# BatteryBoardV1.net
KiCad netlist of a schematic drawn in EAGLE
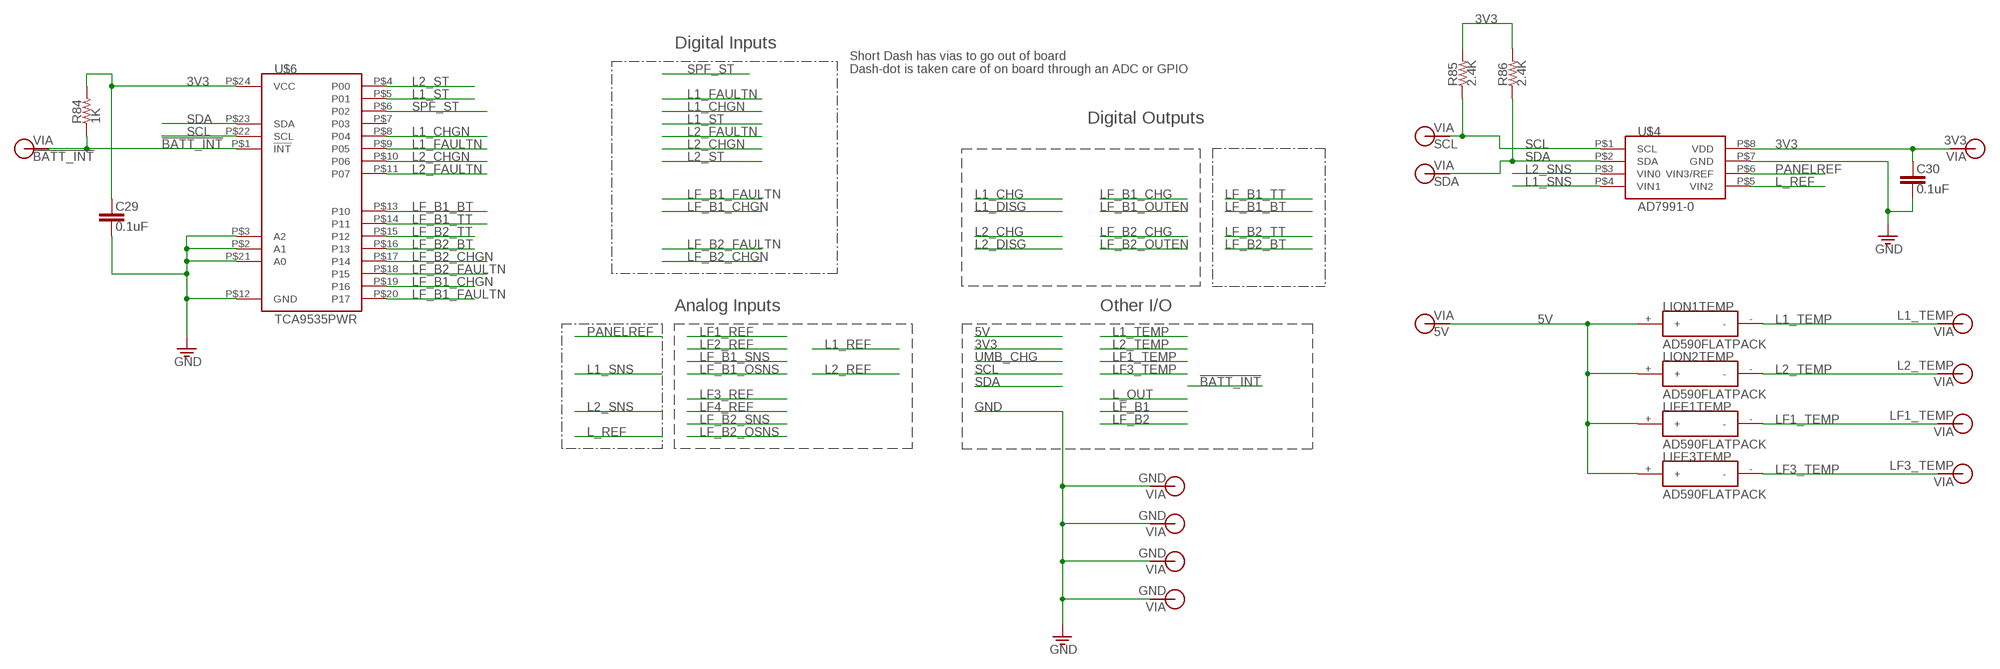
[diagram p0: schematic, sheet 1]
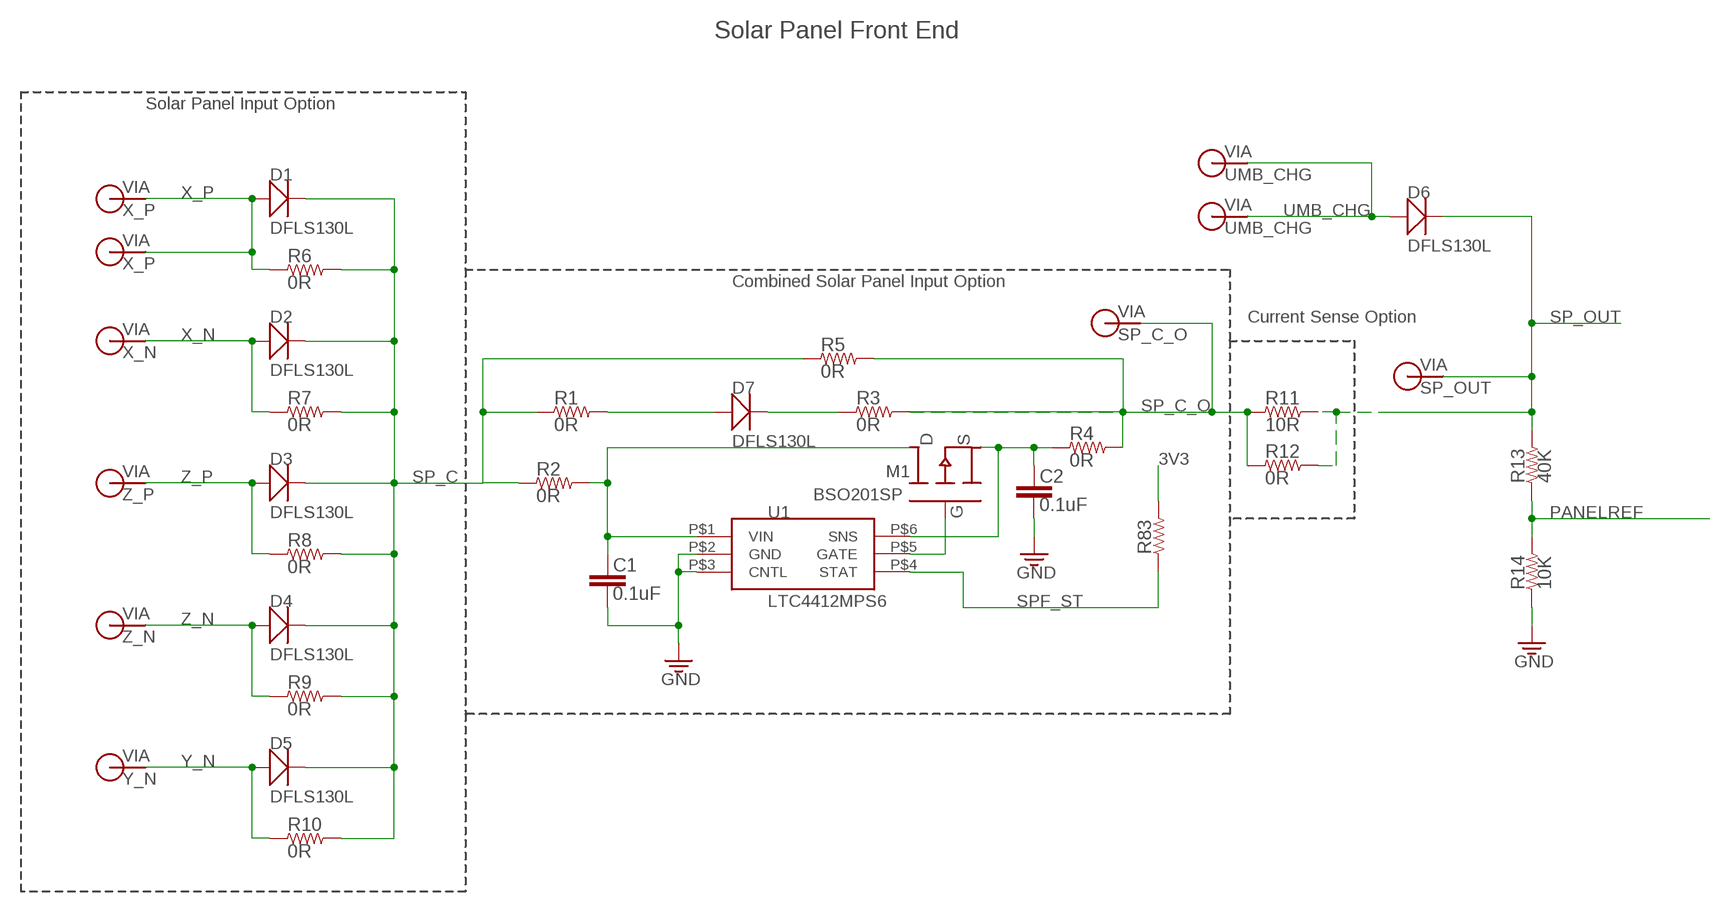
[diagram p1: schematic, sheet 2]
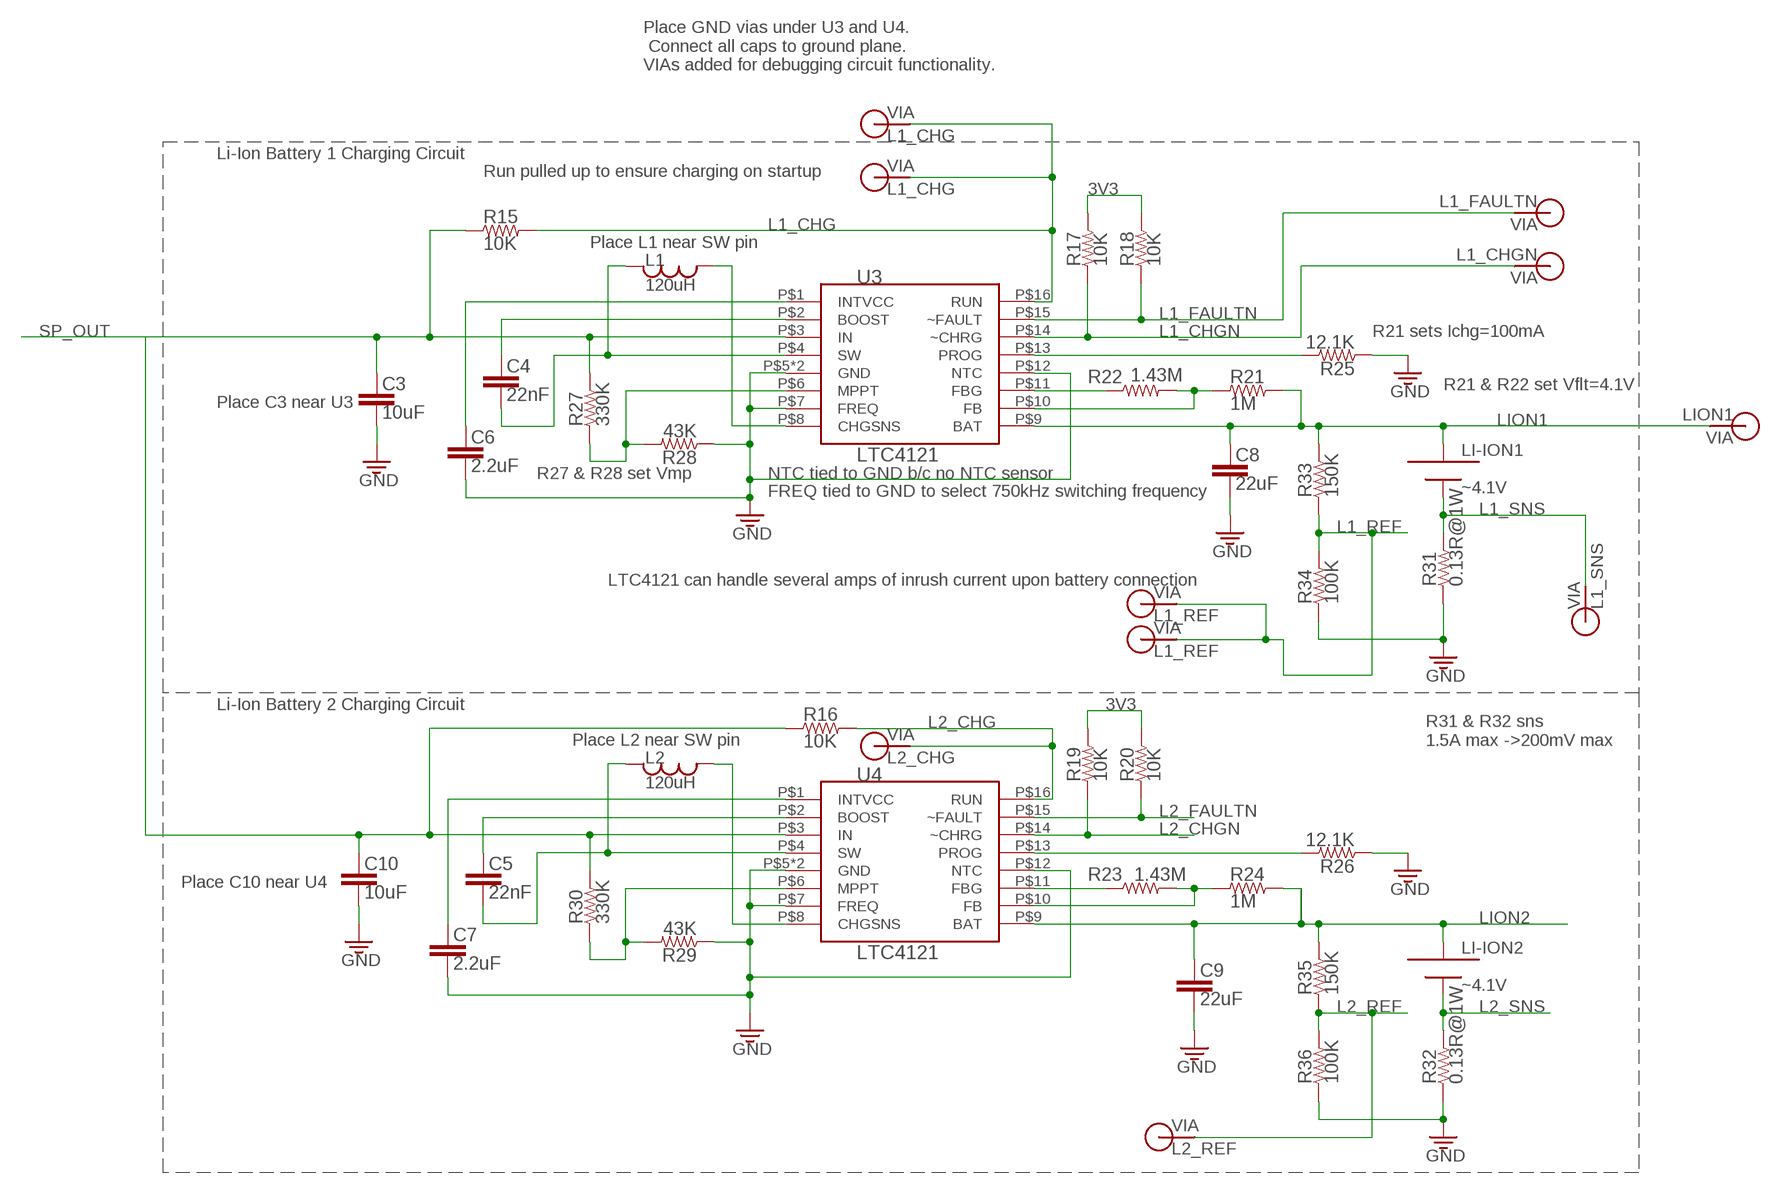
[diagram p2: schematic, sheet 3]
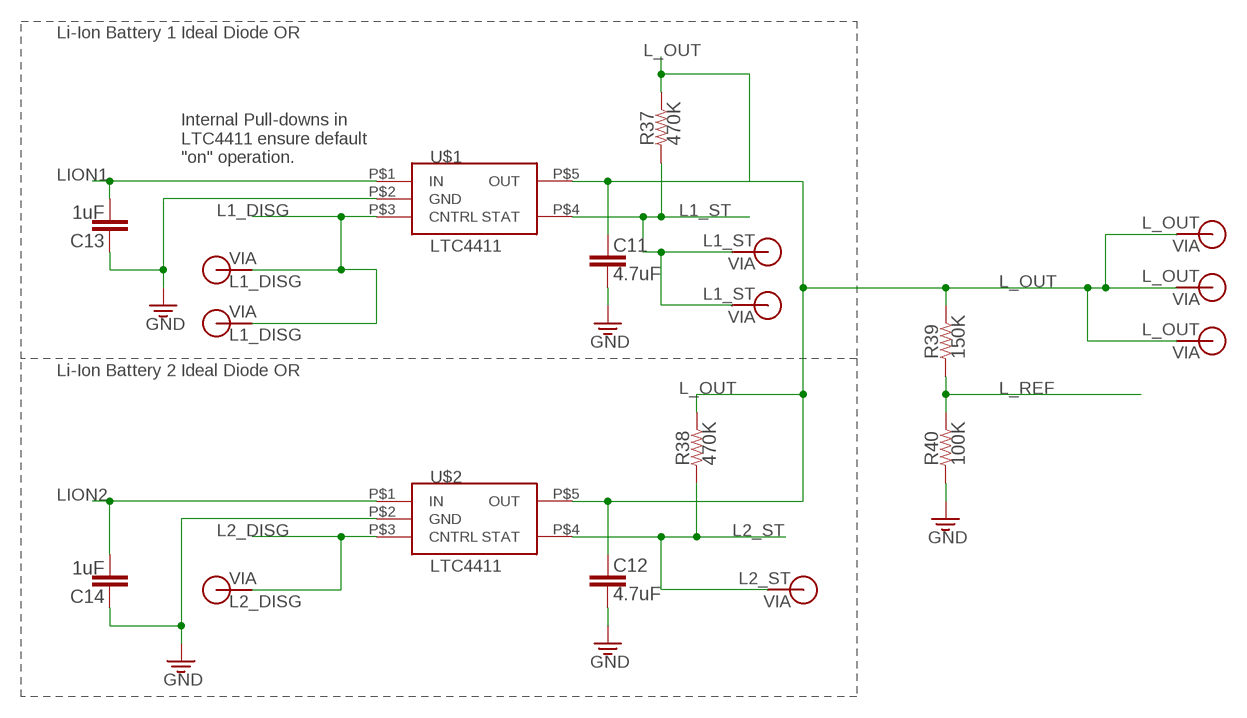
[diagram p3: schematic, sheet 4]
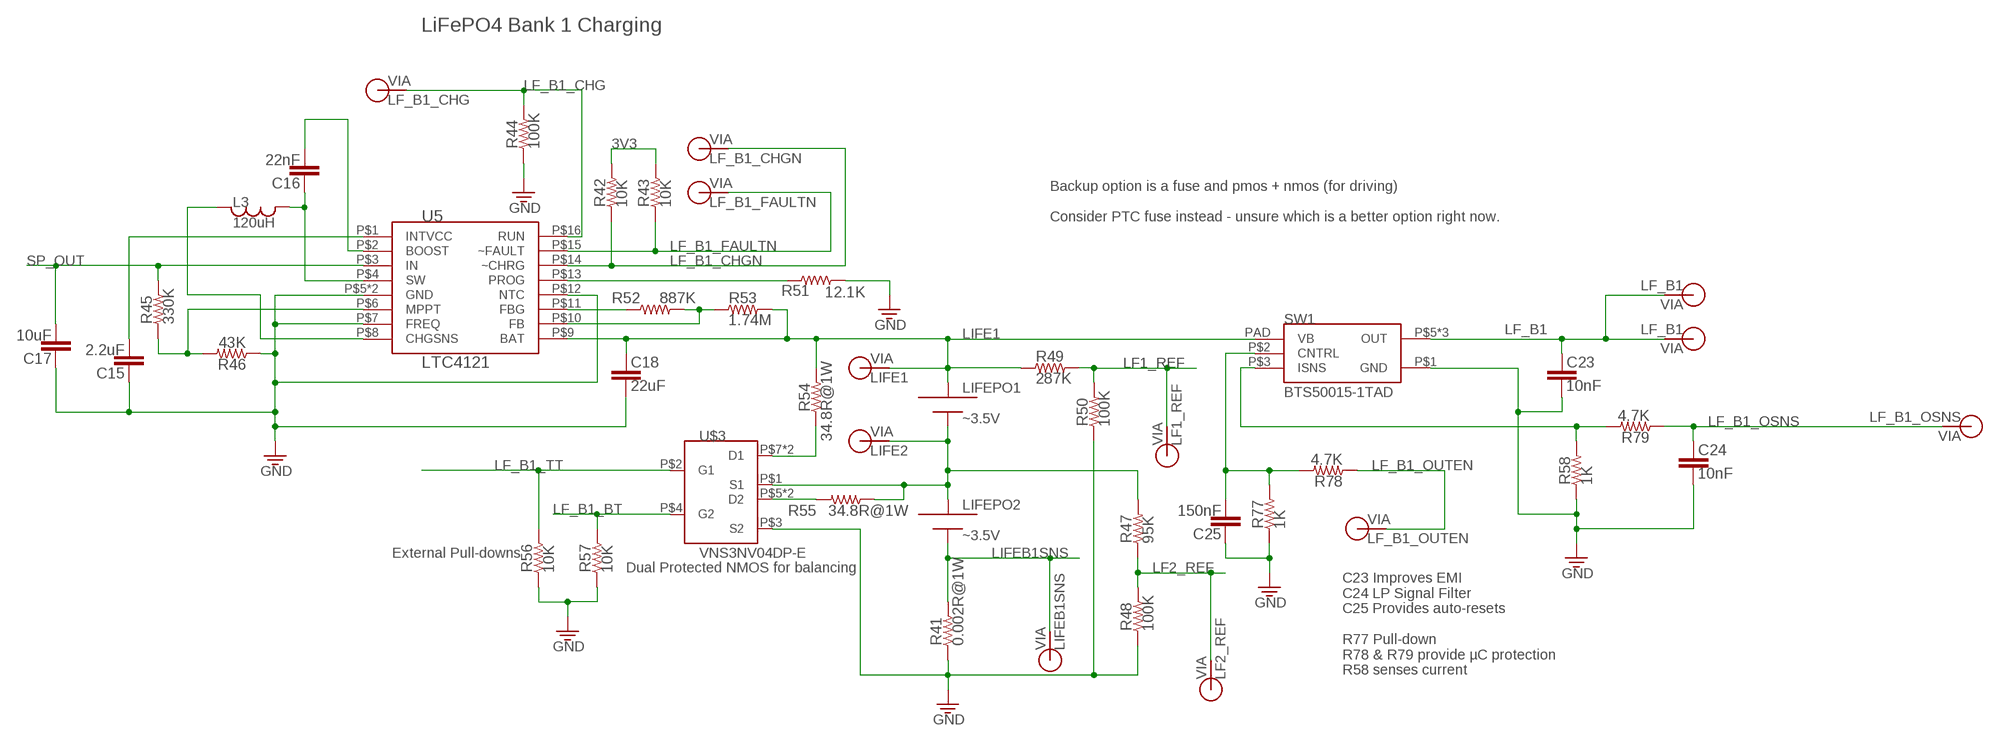
[diagram p4: schematic, sheet 5]
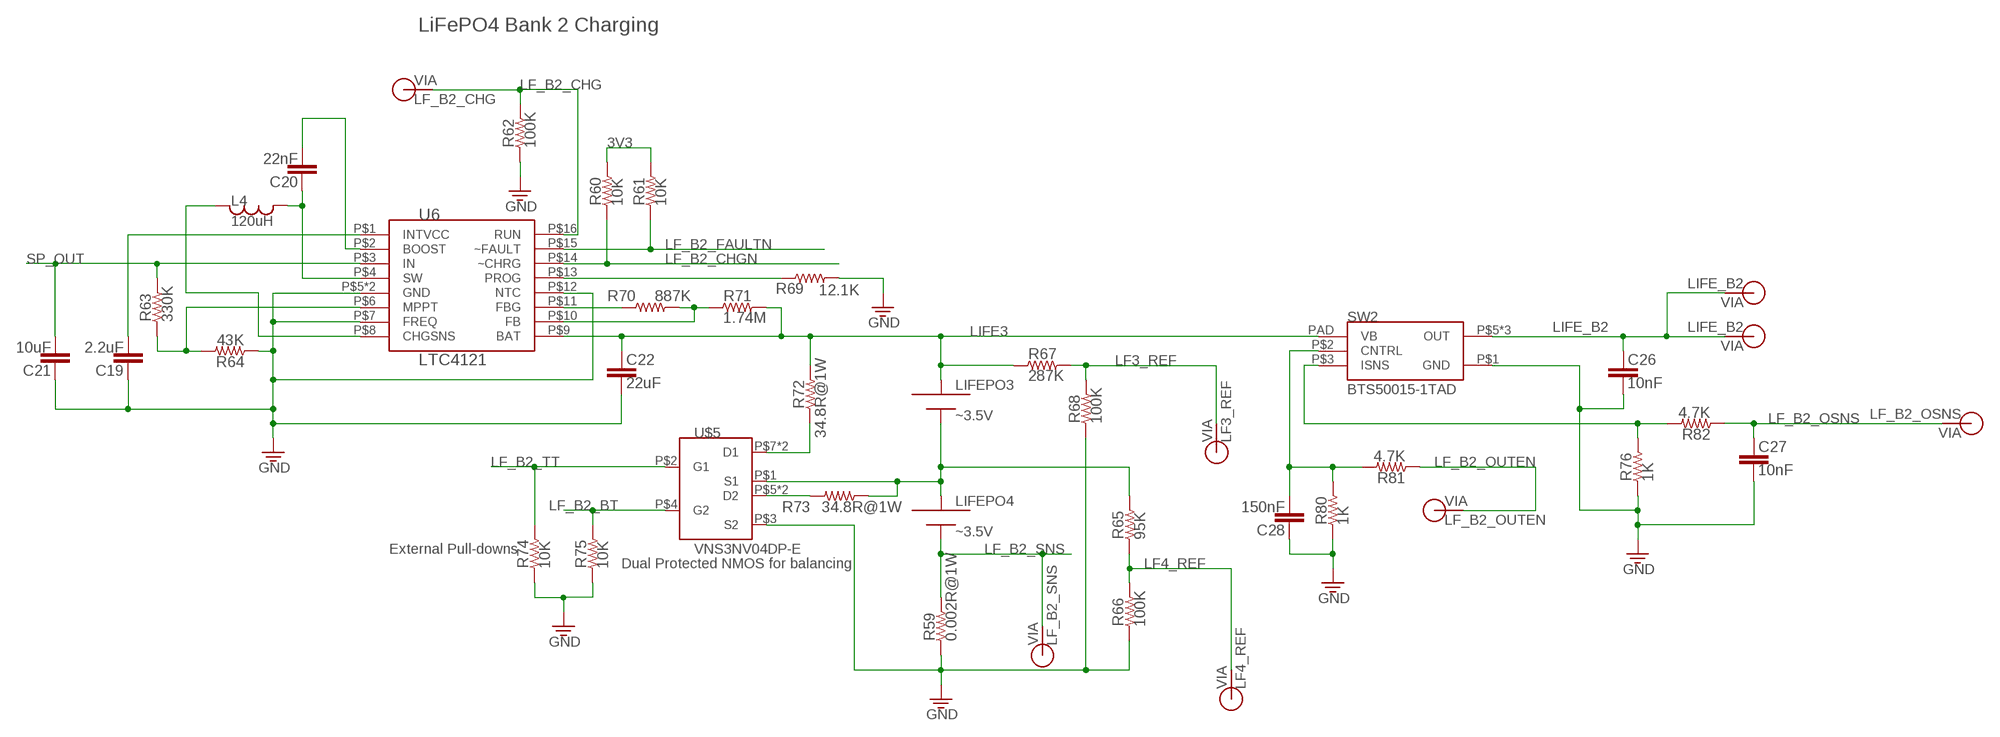
[diagram p5: schematic, sheet 6]

(export (version "E")
  (design (tool "Eeschema 10.0.6"))
  (components
    (comp (ref "C15")
      (value "2.2uF")
      (footprint "eagle-import:0805")
      (libsource (lib "eagle-import") (part "CAP0805"))
    )
    (comp (ref "C16")
      (value "22nF")
      (footprint "eagle-import:0805")
      (libsource (lib "eagle-import") (part "CAP0805"))
    )
    (comp (ref "C17")
      (value "10uF")
      (footprint "eagle-import:0805")
      (libsource (lib "eagle-import") (part "CAP0805"))
    )
    (comp (ref "C18")
      (value "22uF")
      (footprint "eagle-import:0805")
      (libsource (lib "eagle-import") (part "CAP0805"))
    )
    (comp (ref "C23")
      (value "10nF")
      (footprint "eagle-import:0805")
      (libsource (lib "eagle-import") (part "CAP0805"))
    )
    (comp (ref "C24")
      (value "10nF")
      (footprint "eagle-import:0805")
      (libsource (lib "eagle-import") (part "CAP0805"))
    )
    (comp (ref "C25")
      (value "150nF")
      (footprint "eagle-import:0805")
      (libsource (lib "eagle-import") (part "CAP0805"))
    )
    (comp (ref "L3")
      (value "120uH")
      (footprint "eagle-import:1812")
      (libsource (lib "eagle-import") (part "IND1812"))
    )
    (comp (ref "LIFEPO1")
      (value "~3.5V")
      (footprint "eagle-import:EQUISAT-BATTERY-VA")
      (libsource (lib "eagle-import") (part "LIFEPO4VA"))
    )
    (comp (ref "LIFEPO2")
      (value "~3.5V")
      (footprint "eagle-import:EQUISAT-BATTERY-VB")
      (libsource (lib "eagle-import") (part "LIFEPO4VB"))
    )
    (comp (ref "R41")
      (value "0.002R@1W")
      (footprint "eagle-import:1210")
      (libsource (lib "eagle-import") (part "RES1210"))
    )
    (comp (ref "R42")
      (value "10K")
      (footprint "eagle-import:0805")
      (libsource (lib "eagle-import") (part "RES0805"))
    )
    (comp (ref "R43")
      (value "10K")
      (footprint "eagle-import:0805")
      (libsource (lib "eagle-import") (part "RES0805"))
    )
    (comp (ref "R44")
      (value "100K")
      (footprint "eagle-import:0805")
      (libsource (lib "eagle-import") (part "RES0805"))
    )
    (comp (ref "R45")
      (value "330K")
      (footprint "eagle-import:0805")
      (libsource (lib "eagle-import") (part "RES0805"))
    )
    (comp (ref "R46")
      (value "43K")
      (footprint "eagle-import:0805")
      (libsource (lib "eagle-import") (part "RES0805"))
    )
    (comp (ref "R47")
      (value "95K")
      (footprint "eagle-import:0805")
      (libsource (lib "eagle-import") (part "RES0805"))
    )
    (comp (ref "R48")
      (value "100K")
      (footprint "eagle-import:0805")
      (libsource (lib "eagle-import") (part "RES0805"))
    )
    (comp (ref "R49")
      (value "287K")
      (footprint "eagle-import:0805")
      (libsource (lib "eagle-import") (part "RES0805"))
    )
    (comp (ref "R50")
      (value "100K")
      (footprint "eagle-import:0805")
      (libsource (lib "eagle-import") (part "RES0805"))
    )
    (comp (ref "R51")
      (value "12.1K")
      (footprint "eagle-import:0805")
      (libsource (lib "eagle-import") (part "RES0805"))
    )
    (comp (ref "R52")
      (value "887K")
      (footprint "eagle-import:0805")
      (libsource (lib "eagle-import") (part "RES0805"))
    )
    (comp (ref "R53")
      (value "1.74M")
      (footprint "eagle-import:0805")
      (libsource (lib "eagle-import") (part "RES0805"))
    )
    (comp (ref "R54")
      (value "34.8R@1W")
      (footprint "eagle-import:1210")
      (libsource (lib "eagle-import") (part "RES1210"))
    )
    (comp (ref "R55")
      (value "34.8R@1W")
      (footprint "eagle-import:1210")
      (libsource (lib "eagle-import") (part "RES1210"))
    )
    (comp (ref "R56")
      (value "10K")
      (footprint "eagle-import:0805")
      (libsource (lib "eagle-import") (part "RES0805"))
    )
    (comp (ref "R57")
      (value "10K")
      (footprint "eagle-import:0805")
      (libsource (lib "eagle-import") (part "RES0805"))
    )
    (comp (ref "R58")
      (value "1K")
      (footprint "eagle-import:0805")
      (libsource (lib "eagle-import") (part "RES0805"))
    )
    (comp (ref "R77")
      (value "1K")
      (footprint "eagle-import:0805")
      (libsource (lib "eagle-import") (part "RES0805"))
    )
    (comp (ref "R78")
      (value "4.7K")
      (footprint "eagle-import:0805")
      (libsource (lib "eagle-import") (part "RES0805"))
    )
    (comp (ref "R79")
      (value "4.7K")
      (footprint "eagle-import:0805")
      (libsource (lib "eagle-import") (part "RES0805"))
    )
    (comp (ref "SW1")
      (value "BTS50015-1TAD")
      (footprint "eagle-import:TO-263-7-8")
      (libsource (lib "eagle-import") (part "BTS50015-1TAD"))
    )
    (comp (ref "U$3")
      (value "VNS3NV04DP-E")
      (footprint "eagle-import:SO-8")
      (libsource (lib "eagle-import") (part "VNS3NV04DP-E"))
    )
    (comp (ref "U5")
      (value "LTC4121")
      (footprint "eagle-import:QFN-16-PAD")
      (libsource (lib "eagle-import") (part "LTC4121"))
    )
    (comp (ref "V14")
      (value "LIFEB1SNS")
      (footprint "eagle-import:VIA-60MIL")
      (libsource (lib "eagle-import") (part "VIA-60MIL"))
    )
    (comp (ref "V15")
      (value "LF_B1_CHG")
      (footprint "eagle-import:VIA-60MIL")
      (libsource (lib "eagle-import") (part "VIA-60MIL"))
    )
    (comp (ref "V16")
      (value "LIFE2")
      (footprint "eagle-import:VIA-60MIL-SQ")
      (libsource (lib "eagle-import") (part "VIA60MIL-SQ"))
    )
    (comp (ref "V17")
      (value "LIFE1")
      (footprint "eagle-import:VIA-60MIL-SQ")
      (libsource (lib "eagle-import") (part "VIA60MIL-SQ"))
    )
    (comp (ref "V18")
      (value "LF_B1_CHGN")
      (footprint "eagle-import:VIA-60MIL")
      (libsource (lib "eagle-import") (part "VIA-60MIL"))
    )
    (comp (ref "V19")
      (value "LF_B1_FAULTN")
      (footprint "eagle-import:VIA-60MIL")
      (libsource (lib "eagle-import") (part "VIA-60MIL"))
    )
    (comp (ref "V20")
      (value "LF_B1_OUTEN")
      (footprint "eagle-import:VIA-60MIL")
      (libsource (lib "eagle-import") (part "VIA-60MIL"))
    )
    (comp (ref "V21")
      (value "LF_B1")
      (footprint "eagle-import:VIA-120MIL")
      (libsource (lib "eagle-import") (part "VIA-120MIL"))
    )
    (comp (ref "V26")
      (value "LF_B1")
      (footprint "eagle-import:VIA-120MIL")
      (libsource (lib "eagle-import") (part "VIA-120MIL"))
    )
    (comp (ref "V31")
      (value "LF_B1_OSNS")
      (footprint "eagle-import:VIA-60MIL")
      (libsource (lib "eagle-import") (part "VIA-60MIL"))
    )
    (comp (ref "V58")
      (value "LF1_REF")
      (footprint "eagle-import:VIA-60MIL")
      (libsource (lib "eagle-import") (part "VIA-60MIL"))
    )
    (comp (ref "V59")
      (value "LF2_REF")
      (footprint "eagle-import:VIA-60MIL")
      (libsource (lib "eagle-import") (part "VIA-60MIL"))
    )
    (comp (ref "C3")
      (value "10uF")
      (footprint "eagle-import:0805")
      (libsource (lib "eagle-import") (part "CAP0805"))
    )
    (comp (ref "C4")
      (value "22nF")
      (footprint "eagle-import:0805")
      (libsource (lib "eagle-import") (part "CAP0805"))
    )
    (comp (ref "C5")
      (value "22nF")
      (footprint "eagle-import:0805")
      (libsource (lib "eagle-import") (part "CAP0805"))
    )
    (comp (ref "C6")
      (value "2.2uF")
      (footprint "eagle-import:0805")
      (libsource (lib "eagle-import") (part "CAP0805"))
    )
    (comp (ref "C7")
      (value "2.2uF")
      (footprint "eagle-import:0805")
      (libsource (lib "eagle-import") (part "CAP0805"))
    )
    (comp (ref "C8")
      (value "22uF")
      (footprint "eagle-import:0805")
      (libsource (lib "eagle-import") (part "CAP0805"))
    )
    (comp (ref "C9")
      (value "22uF")
      (footprint "eagle-import:0805")
      (libsource (lib "eagle-import") (part "CAP0805"))
    )
    (comp (ref "C10")
      (value "10uF")
      (footprint "eagle-import:0805")
      (libsource (lib "eagle-import") (part "CAP0805"))
    )
    (comp (ref "L1")
      (value "120uH")
      (footprint "eagle-import:1812")
      (libsource (lib "eagle-import") (part "IND1812"))
    )
    (comp (ref "L2")
      (value "120uH")
      (footprint "eagle-import:1812")
      (libsource (lib "eagle-import") (part "IND1812"))
    )
    (comp (ref "LI-ION1")
      (value "~4.1V")
      (footprint "eagle-import:EQUISAT-BATTERY-VA")
      (libsource (lib "eagle-import") (part "LI-ION"))
    )
    (comp (ref "LI-ION2")
      (value "~4.1V")
      (footprint "eagle-import:EQUISAT-BATTERY-VA")
      (libsource (lib "eagle-import") (part "LI-ION"))
    )
    (comp (ref "R15")
      (value "10K")
      (footprint "eagle-import:0805")
      (libsource (lib "eagle-import") (part "RES0805"))
    )
    (comp (ref "R16")
      (value "10K")
      (footprint "eagle-import:0805")
      (libsource (lib "eagle-import") (part "RES0805"))
    )
    (comp (ref "R17")
      (value "10K")
      (footprint "eagle-import:0805")
      (libsource (lib "eagle-import") (part "RES0805"))
    )
    (comp (ref "R18")
      (value "10K")
      (footprint "eagle-import:0805")
      (libsource (lib "eagle-import") (part "RES0805"))
    )
    (comp (ref "R19")
      (value "10K")
      (footprint "eagle-import:0805")
      (libsource (lib "eagle-import") (part "RES0805"))
    )
    (comp (ref "R20")
      (value "10K")
      (footprint "eagle-import:0805")
      (libsource (lib "eagle-import") (part "RES0805"))
    )
    (comp (ref "R21")
      (value "1M")
      (footprint "eagle-import:0805")
      (libsource (lib "eagle-import") (part "RES0805"))
    )
    (comp (ref "R22")
      (value "1.43M")
      (footprint "eagle-import:0805")
      (libsource (lib "eagle-import") (part "RES0805"))
    )
    (comp (ref "R23")
      (value "1.43M")
      (footprint "eagle-import:0805")
      (libsource (lib "eagle-import") (part "RES0805"))
    )
    (comp (ref "R24")
      (value "1M")
      (footprint "eagle-import:0805")
      (libsource (lib "eagle-import") (part "RES0805"))
    )
    (comp (ref "R25")
      (value "12.1K")
      (footprint "eagle-import:0805")
      (libsource (lib "eagle-import") (part "RES0805"))
    )
    (comp (ref "R26")
      (value "12.1K")
      (footprint "eagle-import:0805")
      (libsource (lib "eagle-import") (part "RES0805"))
    )
    (comp (ref "R27")
      (value "330K")
      (footprint "eagle-import:0805")
      (libsource (lib "eagle-import") (part "RES0805"))
    )
    (comp (ref "R28")
      (value "43K")
      (footprint "eagle-import:0805")
      (libsource (lib "eagle-import") (part "RES0805"))
    )
    (comp (ref "R29")
      (value "43K")
      (footprint "eagle-import:0805")
      (libsource (lib "eagle-import") (part "RES0805"))
    )
    (comp (ref "R30")
      (value "330K")
      (footprint "eagle-import:0805")
      (libsource (lib "eagle-import") (part "RES0805"))
    )
    (comp (ref "R31")
      (value "0.13R@1W")
      (footprint "eagle-import:1210")
      (libsource (lib "eagle-import") (part "RES1210"))
    )
    (comp (ref "R32")
      (value "0.13R@1W")
      (footprint "eagle-import:1210")
      (libsource (lib "eagle-import") (part "RES1210"))
    )
    (comp (ref "R33")
      (value "150K")
      (footprint "eagle-import:0805")
      (libsource (lib "eagle-import") (part "RES0805"))
    )
    (comp (ref "R34")
      (value "100K")
      (footprint "eagle-import:0805")
      (libsource (lib "eagle-import") (part "RES0805"))
    )
    (comp (ref "R35")
      (value "150K")
      (footprint "eagle-import:0805")
      (libsource (lib "eagle-import") (part "RES0805"))
    )
    (comp (ref "R36")
      (value "100K")
      (footprint "eagle-import:0805")
      (libsource (lib "eagle-import") (part "RES0805"))
    )
    (comp (ref "U3")
      (value "LTC4121")
      (footprint "eagle-import:QFN-16-PAD")
      (libsource (lib "eagle-import") (part "LTC4121"))
    )
    (comp (ref "U4")
      (value "LTC4121")
      (footprint "eagle-import:QFN-16-PAD")
      (libsource (lib "eagle-import") (part "LTC4121"))
    )
    (comp (ref "V10")
      (value "L1_CHG")
      (footprint "eagle-import:VIA-60MIL")
      (libsource (lib "eagle-import") (part "VIA-60MIL"))
    )
    (comp (ref "V25")
      (value "L1_REF")
      (footprint "eagle-import:VIA-60MIL")
      (libsource (lib "eagle-import") (part "VIA-60MIL"))
    )
    (comp (ref "V29")
      (value "L2_REF")
      (footprint "eagle-import:VIA-60MIL")
      (libsource (lib "eagle-import") (part "VIA-60MIL"))
    )
    (comp (ref "V33")
      (value "L2_CHG")
      (footprint "eagle-import:VIA-60MIL")
      (libsource (lib "eagle-import") (part "VIA-60MIL"))
    )
    (comp (ref "V40")
      (value "L1_CHG")
      (footprint "eagle-import:VIA-60MIL-SQ")
      (libsource (lib "eagle-import") (part "VIA60MIL-SQ"))
    )
    (comp (ref "V41")
      (value "L1_FAULTN")
      (footprint "eagle-import:VIA-60MIL-SQ")
      (libsource (lib "eagle-import") (part "VIA60MIL-SQ"))
    )
    (comp (ref "V42")
      (value "L1_CHGN")
      (footprint "eagle-import:VIA-60MIL-SQ")
      (libsource (lib "eagle-import") (part "VIA60MIL-SQ"))
    )
    (comp (ref "V43")
      (value "L1_SNS")
      (footprint "eagle-import:VIA-60MIL-SQ")
      (libsource (lib "eagle-import") (part "VIA60MIL-SQ"))
    )
    (comp (ref "V44")
      (value "L1_REF")
      (footprint "eagle-import:VIA-60MIL-SQ")
      (libsource (lib "eagle-import") (part "VIA60MIL-SQ"))
    )
    (comp (ref "V45")
      (value "LION1")
      (footprint "eagle-import:VIA-60MIL-SQ")
      (libsource (lib "eagle-import") (part "VIA60MIL-SQ"))
    )
    (comp (ref "C19")
      (value "2.2uF")
      (footprint "eagle-import:0805")
      (libsource (lib "eagle-import") (part "CAP0805"))
    )
    (comp (ref "C20")
      (value "22nF")
      (footprint "eagle-import:0805")
      (libsource (lib "eagle-import") (part "CAP0805"))
    )
    (comp (ref "C21")
      (value "10uF")
      (footprint "eagle-import:0805")
      (libsource (lib "eagle-import") (part "CAP0805"))
    )
    (comp (ref "C22")
      (value "22uF")
      (footprint "eagle-import:0805")
      (libsource (lib "eagle-import") (part "CAP0805"))
    )
    (comp (ref "C26")
      (value "10nF")
      (footprint "eagle-import:0805")
      (libsource (lib "eagle-import") (part "CAP0805"))
    )
    (comp (ref "C27")
      (value "10nF")
      (footprint "eagle-import:0805")
      (libsource (lib "eagle-import") (part "CAP0805"))
    )
    (comp (ref "C28")
      (value "150nF")
      (footprint "eagle-import:0805")
      (libsource (lib "eagle-import") (part "CAP0805"))
    )
    (comp (ref "L4")
      (value "120uH")
      (footprint "eagle-import:1812")
      (libsource (lib "eagle-import") (part "IND1812"))
    )
    (comp (ref "LIFEPO3")
      (value "~3.5V")
      (footprint "eagle-import:EQUISAT-BATTERY-VA")
      (libsource (lib "eagle-import") (part "LIFEPO4VA"))
    )
    (comp (ref "LIFEPO4")
      (value "~3.5V")
      (footprint "eagle-import:EQUISAT-BATTERY-VB")
      (libsource (lib "eagle-import") (part "LIFEPO4VB"))
    )
    (comp (ref "R59")
      (value "0.002R@1W")
      (footprint "eagle-import:1210")
      (libsource (lib "eagle-import") (part "RES1210"))
    )
    (comp (ref "R60")
      (value "10K")
      (footprint "eagle-import:0805")
      (libsource (lib "eagle-import") (part "RES0805"))
    )
    (comp (ref "R61")
      (value "10K")
      (footprint "eagle-import:0805")
      (libsource (lib "eagle-import") (part "RES0805"))
    )
    (comp (ref "R62")
      (value "100K")
      (footprint "eagle-import:0805")
      (libsource (lib "eagle-import") (part "RES0805"))
    )
    (comp (ref "R63")
      (value "330K")
      (footprint "eagle-import:0805")
      (libsource (lib "eagle-import") (part "RES0805"))
    )
    (comp (ref "R64")
      (value "43K")
      (footprint "eagle-import:0805")
      (libsource (lib "eagle-import") (part "RES0805"))
    )
    (comp (ref "R65")
      (value "95K")
      (footprint "eagle-import:0805")
      (libsource (lib "eagle-import") (part "RES0805"))
    )
    (comp (ref "R66")
      (value "100K")
      (footprint "eagle-import:0805")
      (libsource (lib "eagle-import") (part "RES0805"))
    )
    (comp (ref "R67")
      (value "287K")
      (footprint "eagle-import:0805")
      (libsource (lib "eagle-import") (part "RES0805"))
    )
    (comp (ref "R68")
      (value "100K")
      (footprint "eagle-import:0805")
      (libsource (lib "eagle-import") (part "RES0805"))
    )
    (comp (ref "R69")
      (value "12.1K")
      (footprint "eagle-import:0805")
      (libsource (lib "eagle-import") (part "RES0805"))
    )
    (comp (ref "R70")
      (value "887K")
      (footprint "eagle-import:0805")
      (libsource (lib "eagle-import") (part "RES0805"))
    )
    (comp (ref "R71")
      (value "1.74M")
      (footprint "eagle-import:0805")
      (libsource (lib "eagle-import") (part "RES0805"))
    )
    (comp (ref "R72")
      (value "34.8R@1W")
      (footprint "eagle-import:1210")
      (libsource (lib "eagle-import") (part "RES1210"))
    )
    (comp (ref "R73")
      (value "34.8R@1W")
      (footprint "eagle-import:1210")
      (libsource (lib "eagle-import") (part "RES1210"))
    )
    (comp (ref "R74")
      (value "10K")
      (footprint "eagle-import:0805")
      (libsource (lib "eagle-import") (part "RES0805"))
    )
    (comp (ref "R75")
      (value "10K")
      (footprint "eagle-import:0805")
      (libsource (lib "eagle-import") (part "RES0805"))
    )
    (comp (ref "R76")
      (value "1K")
      (footprint "eagle-import:0805")
      (libsource (lib "eagle-import") (part "RES0805"))
    )
    (comp (ref "R80")
      (value "1K")
      (footprint "eagle-import:0805")
      (libsource (lib "eagle-import") (part "RES0805"))
    )
    (comp (ref "R81")
      (value "4.7K")
      (footprint "eagle-import:0805")
      (libsource (lib "eagle-import") (part "RES0805"))
    )
    (comp (ref "R82")
      (value "4.7K")
      (footprint "eagle-import:0805")
      (libsource (lib "eagle-import") (part "RES0805"))
    )
    (comp (ref "SW2")
      (value "BTS50015-1TAD")
      (footprint "eagle-import:TO-263-7-8")
      (libsource (lib "eagle-import") (part "BTS50015-1TAD"))
    )
    (comp (ref "U$5")
      (value "VNS3NV04DP-E")
      (footprint "eagle-import:SO-8")
      (libsource (lib "eagle-import") (part "VNS3NV04DP-E"))
    )
    (comp (ref "U6")
      (value "LTC4121")
      (footprint "eagle-import:QFN-16-PAD")
      (libsource (lib "eagle-import") (part "LTC4121"))
    )
    (comp (ref "V27")
      (value "LIFE_B2")
      (footprint "eagle-import:VIA-120MIL")
      (libsource (lib "eagle-import") (part "VIA-120MIL"))
    )
    (comp (ref "V28")
      (value "LIFE_B2")
      (footprint "eagle-import:VIA-120MIL")
      (libsource (lib "eagle-import") (part "VIA-120MIL"))
    )
    (comp (ref "V56")
      (value "LF_B2_OUTEN")
      (footprint "eagle-import:VIA-60MIL")
      (libsource (lib "eagle-import") (part "VIA-60MIL"))
    )
    (comp (ref "V57")
      (value "LF_B2_CHG")
      (footprint "eagle-import:VIA-60MIL")
      (libsource (lib "eagle-import") (part "VIA-60MIL"))
    )
    (comp (ref "V60")
      (value "LF_B2_SNS")
      (footprint "eagle-import:VIA-60MIL")
      (libsource (lib "eagle-import") (part "VIA-60MIL"))
    )
    (comp (ref "V61")
      (value "LF4_REF")
      (footprint "eagle-import:VIA-60MIL")
      (libsource (lib "eagle-import") (part "VIA-60MIL"))
    )
    (comp (ref "V62")
      (value "LF3_REF")
      (footprint "eagle-import:VIA-60MIL")
      (libsource (lib "eagle-import") (part "VIA-60MIL"))
    )
    (comp (ref "V63")
      (value "LF_B2_OSNS")
      (footprint "eagle-import:VIA-60MIL")
      (libsource (lib "eagle-import") (part "VIA-60MIL"))
    )
    (comp (ref "C11")
      (value "4.7uF")
      (footprint "eagle-import:0805")
      (libsource (lib "eagle-import") (part "CAP0805"))
    )
    (comp (ref "C12")
      (value "4.7uF")
      (footprint "eagle-import:0805")
      (libsource (lib "eagle-import") (part "CAP0805"))
    )
    (comp (ref "C13")
      (value "1uF")
      (footprint "eagle-import:0805")
      (libsource (lib "eagle-import") (part "CAP0805"))
    )
    (comp (ref "C14")
      (value "1uF")
      (footprint "eagle-import:0805")
      (libsource (lib "eagle-import") (part "CAP0805"))
    )
    (comp (ref "R37")
      (value "470K")
      (footprint "eagle-import:0805")
      (libsource (lib "eagle-import") (part "RES0805"))
    )
    (comp (ref "R38")
      (value "470K")
      (footprint "eagle-import:0805")
      (libsource (lib "eagle-import") (part "RES0805"))
    )
    (comp (ref "R39")
      (value "150K")
      (footprint "eagle-import:0805")
      (libsource (lib "eagle-import") (part "RES0805"))
    )
    (comp (ref "R40")
      (value "100K")
      (footprint "eagle-import:0805")
      (libsource (lib "eagle-import") (part "RES0805"))
    )
    (comp (ref "U$1")
      (value "LTC4411")
      (footprint "eagle-import:TSOT23-5")
      (libsource (lib "eagle-import") (part "LTC4411"))
    )
    (comp (ref "U$2")
      (value "LTC4411")
      (footprint "eagle-import:TSOT23-5")
      (libsource (lib "eagle-import") (part "LTC4411"))
    )
    (comp (ref "V30")
      (value "L_OUT")
      (footprint "eagle-import:VIA-120MIL")
      (libsource (lib "eagle-import") (part "VIA-120MIL"))
    )
    (comp (ref "V34")
      (value "L1_DISG")
      (footprint "eagle-import:VIA-60MIL")
      (libsource (lib "eagle-import") (part "VIA-60MIL"))
    )
    (comp (ref "V35")
      (value "L2_DISG")
      (footprint "eagle-import:VIA-60MIL")
      (libsource (lib "eagle-import") (part "VIA-60MIL"))
    )
    (comp (ref "V36")
      (value "L1_ST")
      (footprint "eagle-import:VIA-60MIL")
      (libsource (lib "eagle-import") (part "VIA-60MIL"))
    )
    (comp (ref "V38")
      (value "L2_ST")
      (footprint "eagle-import:VIA-60MIL")
      (libsource (lib "eagle-import") (part "VIA-60MIL"))
    )
    (comp (ref "V46")
      (value "L1_DISG")
      (footprint "eagle-import:VIA-60MIL-SQ")
      (libsource (lib "eagle-import") (part "VIA60MIL-SQ"))
    )
    (comp (ref "V47")
      (value "L1_ST")
      (footprint "eagle-import:VIA-60MIL-SQ")
      (libsource (lib "eagle-import") (part "VIA60MIL-SQ"))
    )
    (comp (ref "V48")
      (value "L_OUT")
      (footprint "eagle-import:VIA-60MIL-SQ")
      (libsource (lib "eagle-import") (part "VIA60MIL-SQ"))
    )
    (comp (ref "V54")
      (value "L_OUT")
      (footprint "eagle-import:VIA-120MIL")
      (libsource (lib "eagle-import") (part "VIA-120MIL"))
    )
    (comp (ref "C29")
      (value "0.1uF")
      (footprint "eagle-import:0805")
      (libsource (lib "eagle-import") (part "CAP0805"))
    )
    (comp (ref "C30")
      (value "0.1uF")
      (footprint "eagle-import:0805")
      (libsource (lib "eagle-import") (part "CAP0805"))
    )
    (comp (ref "LIFE1TEMP")
      (value "AD590FLATPACK")
      (footprint "eagle-import:FLATPACK")
      (libsource (lib "eagle-import") (part "AD590FLATPACK"))
    )
    (comp (ref "LIFE3TEMP")
      (value "AD590FLATPACK")
      (footprint "eagle-import:FLATPACK")
      (libsource (lib "eagle-import") (part "AD590FLATPACK"))
    )
    (comp (ref "LION1TEMP")
      (value "AD590FLATPACK")
      (footprint "eagle-import:FLATPACK")
      (libsource (lib "eagle-import") (part "AD590FLATPACK"))
    )
    (comp (ref "LION2TEMP")
      (value "AD590FLATPACK")
      (footprint "eagle-import:FLATPACK")
      (libsource (lib "eagle-import") (part "AD590FLATPACK"))
    )
    (comp (ref "R84")
      (value "1K")
      (footprint "eagle-import:0805")
      (libsource (lib "eagle-import") (part "RES0805"))
    )
    (comp (ref "R85")
      (value "2.4K")
      (footprint "eagle-import:0805")
      (libsource (lib "eagle-import") (part "RES0805"))
    )
    (comp (ref "R86")
      (value "2.4K")
      (footprint "eagle-import:0805")
      (libsource (lib "eagle-import") (part "RES0805"))
    )
    (comp (ref "U$4")
      (value "AD7991-0")
      (footprint "eagle-import:SOT-23-8")
      (libsource (lib "eagle-import") (part "AD7991-0"))
    )
    (comp (ref "U$6")
      (value "TCA9535PWR")
      (footprint "eagle-import:TSSOP-24")
      (libsource (lib "eagle-import") (part "TCA9535PWR"))
    )
    (comp (ref "V9")
      (value "5V")
      (footprint "eagle-import:VIA-60MIL")
      (libsource (lib "eagle-import") (part "VIA-60MIL"))
    )
    (comp (ref "V11")
      (value "!BATT_INT!")
      (footprint "eagle-import:VIA-60MIL")
      (libsource (lib "eagle-import") (part "VIA-60MIL"))
    )
    (comp (ref "V12")
      (value "GND")
      (footprint "eagle-import:VIA-60MIL-SQ")
      (libsource (lib "eagle-import") (part "VIA60MIL-SQ"))
    )
    (comp (ref "V13")
      (value "GND")
      (footprint "eagle-import:VIA-120MIL")
      (libsource (lib "eagle-import") (part "VIA-120MIL"))
    )
    (comp (ref "V22")
      (value "GND")
      (footprint "eagle-import:VIA-120MIL")
      (libsource (lib "eagle-import") (part "VIA-120MIL"))
    )
    (comp (ref "V23")
      (value "GND")
      (footprint "eagle-import:VIA-120MIL")
      (libsource (lib "eagle-import") (part "VIA-120MIL"))
    )
    (comp (ref "V24")
      (value "L1_TEMP")
      (footprint "eagle-import:VIA-60MIL")
      (libsource (lib "eagle-import") (part "VIA-60MIL"))
    )
    (comp (ref "V32")
      (value "L2_TEMP")
      (footprint "eagle-import:VIA-60MIL")
      (libsource (lib "eagle-import") (part "VIA-60MIL"))
    )
    (comp (ref "V37")
      (value "LF1_TEMP")
      (footprint "eagle-import:VIA-60MIL")
      (libsource (lib "eagle-import") (part "VIA-60MIL"))
    )
    (comp (ref "V50")
      (value "LF3_TEMP")
      (footprint "eagle-import:VIA-60MIL")
      (libsource (lib "eagle-import") (part "VIA-60MIL"))
    )
    (comp (ref "V51")
      (value "3V3")
      (footprint "eagle-import:VIA-60MIL")
      (libsource (lib "eagle-import") (part "VIA-60MIL"))
    )
    (comp (ref "V52")
      (value "SCL")
      (footprint "eagle-import:VIA-60MIL")
      (libsource (lib "eagle-import") (part "VIA-60MIL"))
    )
    (comp (ref "V53")
      (value "SDA")
      (footprint "eagle-import:VIA-60MIL")
      (libsource (lib "eagle-import") (part "VIA-60MIL"))
    )
    (comp (ref "C1")
      (value "0.1uF")
      (footprint "eagle-import:0805")
      (libsource (lib "eagle-import") (part "CAP0805"))
    )
    (comp (ref "C2")
      (value "0.1uF")
      (footprint "eagle-import:0805")
      (libsource (lib "eagle-import") (part "CAP0805"))
    )
    (comp (ref "D1")
      (value "DFLS130L")
      (footprint "eagle-import:PWRDI-123")
      (libsource (lib "eagle-import") (part "DFLS130L"))
    )
    (comp (ref "D2")
      (value "DFLS130L")
      (footprint "eagle-import:PWRDI-123")
      (libsource (lib "eagle-import") (part "DFLS130L"))
    )
    (comp (ref "D3")
      (value "DFLS130L")
      (footprint "eagle-import:PWRDI-123")
      (libsource (lib "eagle-import") (part "DFLS130L"))
    )
    (comp (ref "D4")
      (value "DFLS130L")
      (footprint "eagle-import:PWRDI-123")
      (libsource (lib "eagle-import") (part "DFLS130L"))
    )
    (comp (ref "D5")
      (value "DFLS130L")
      (footprint "eagle-import:PWRDI-123")
      (libsource (lib "eagle-import") (part "DFLS130L"))
    )
    (comp (ref "D6")
      (value "DFLS130L")
      (footprint "eagle-import:PWRDI-123")
      (libsource (lib "eagle-import") (part "DFLS130L"))
    )
    (comp (ref "D7")
      (value "DFLS130L")
      (footprint "eagle-import:PWRDI-123")
      (libsource (lib "eagle-import") (part "DFLS130L"))
    )
    (comp (ref "M1")
      (value "BSO201SP")
      (footprint "eagle-import:SO-8")
      (libsource (lib "eagle-import") (part "BSO201SP"))
    )
    (comp (ref "R1")
      (value "0R")
      (footprint "eagle-import:0805")
      (libsource (lib "eagle-import") (part "RES0805"))
    )
    (comp (ref "R2")
      (value "0R")
      (footprint "eagle-import:0805")
      (libsource (lib "eagle-import") (part "RES0805"))
    )
    (comp (ref "R3")
      (value "0R")
      (footprint "eagle-import:0805")
      (libsource (lib "eagle-import") (part "RES0805"))
    )
    (comp (ref "R4")
      (value "0R")
      (footprint "eagle-import:0805")
      (libsource (lib "eagle-import") (part "RES0805"))
    )
    (comp (ref "R5")
      (value "0R")
      (footprint "eagle-import:0805")
      (libsource (lib "eagle-import") (part "RES0805"))
    )
    (comp (ref "R6")
      (value "0R")
      (footprint "eagle-import:0805")
      (libsource (lib "eagle-import") (part "RES0805"))
    )
    (comp (ref "R7")
      (value "0R")
      (footprint "eagle-import:0805")
      (libsource (lib "eagle-import") (part "RES0805"))
    )
    (comp (ref "R8")
      (value "0R")
      (footprint "eagle-import:0805")
      (libsource (lib "eagle-import") (part "RES0805"))
    )
    (comp (ref "R9")
      (value "0R")
      (footprint "eagle-import:0805")
      (libsource (lib "eagle-import") (part "RES0805"))
    )
    (comp (ref "R10")
      (value "0R")
      (footprint "eagle-import:0805")
      (libsource (lib "eagle-import") (part "RES0805"))
    )
    (comp (ref "R11")
      (value "10R")
      (footprint "eagle-import:0805")
      (libsource (lib "eagle-import") (part "RES0805"))
    )
    (comp (ref "R12")
      (value "0R")
      (footprint "eagle-import:0805")
      (libsource (lib "eagle-import") (part "RES0805"))
    )
    (comp (ref "R13")
      (value "40K")
      (footprint "eagle-import:0805")
      (libsource (lib "eagle-import") (part "RES0805"))
    )
    (comp (ref "R14")
      (value "10K")
      (footprint "eagle-import:0805")
      (libsource (lib "eagle-import") (part "RES0805"))
    )
    (comp (ref "R83")
      (value "RES0805")
      (footprint "eagle-import:0805")
      (libsource (lib "eagle-import") (part "RES0805"))
    )
    (comp (ref "U1")
      (value "LTC4412MPS6")
      (footprint "eagle-import:TSOT23-6")
      (libsource (lib "eagle-import") (part "LTC4412"))
    )
    (comp (ref "V1")
      (value "UMB_CHG")
      (footprint "eagle-import:VIA-60MIL")
      (libsource (lib "eagle-import") (part "VIA-60MIL"))
    )
    (comp (ref "V2")
      (value "X_P")
      (footprint "eagle-import:VIA-60MIL")
      (libsource (lib "eagle-import") (part "VIA-60MIL"))
    )
    (comp (ref "V3")
      (value "X_N")
      (footprint "eagle-import:VIA-60MIL")
      (libsource (lib "eagle-import") (part "VIA-60MIL"))
    )
    (comp (ref "V4")
      (value "Z_P")
      (footprint "eagle-import:VIA-60MIL")
      (libsource (lib "eagle-import") (part "VIA-60MIL"))
    )
    (comp (ref "V5")
      (value "Z_N")
      (footprint "eagle-import:VIA-60MIL")
      (libsource (lib "eagle-import") (part "VIA-60MIL"))
    )
    (comp (ref "V6")
      (value "Y_N")
      (footprint "eagle-import:VIA-60MIL")
      (libsource (lib "eagle-import") (part "VIA-60MIL"))
    )
    (comp (ref "V7")
      (value "SP_C_O")
      (footprint "eagle-import:VIA-60MIL-SQ")
      (libsource (lib "eagle-import") (part "VIA60MIL-SQ"))
    )
    (comp (ref "V8")
      (value "SP_OUT")
      (footprint "eagle-import:VIA-60MIL-SQ")
      (libsource (lib "eagle-import") (part "VIA60MIL-SQ"))
    )
    (comp (ref "V39")
      (value "UMB_CHG")
      (footprint "eagle-import:VIA-60MIL-SQ")
      (libsource (lib "eagle-import") (part "VIA60MIL-SQ"))
    )
    (comp (ref "V49")
      (value "X_P")
      (footprint "eagle-import:VIA-60MIL-SQ")
      (libsource (lib "eagle-import") (part "VIA60MIL-SQ"))
    )
  )
  (nets
    (net (code "1") (name "3V3") (class "Default")
      (node (ref "C29") (pin "1") (pinfunction "P$1_1") (pintype "passive"))
      (node (ref "C30") (pin "1") (pinfunction "P$1_1") (pintype "passive"))
      (node (ref "R17") (pin "2") (pinfunction "2_2") (pintype "passive"))
      (node (ref "R18") (pin "2") (pinfunction "2_2") (pintype "passive"))
      (node (ref "R19") (pin "2") (pinfunction "2_2") (pintype "passive"))
      (node (ref "R20") (pin "2") (pinfunction "2_2") (pintype "passive"))
      (node (ref "R42") (pin "2") (pinfunction "2_2") (pintype "passive"))
      (node (ref "R43") (pin "2") (pinfunction "2_2") (pintype "passive"))
      (node (ref "R60") (pin "2") (pinfunction "2_2") (pintype "passive"))
      (node (ref "R61") (pin "2") (pinfunction "2_2") (pintype "passive"))
      (node (ref "R83") (pin "2") (pinfunction "2_2") (pintype "passive"))
      (node (ref "R84") (pin "2") (pinfunction "2_2") (pintype "passive"))
      (node (ref "R85") (pin "2") (pinfunction "2_2") (pintype "passive"))
      (node (ref "R86") (pin "2") (pinfunction "2_2") (pintype "passive"))
      (node (ref "U$4") (pin "P$8") (pinfunction "VDD_P$8") (pintype "bidirectional"))
      (node (ref "U$6") (pin "P$24") (pinfunction "VCC_P$24") (pintype "power_in"))
      (node (ref "V51") (pin "P$1") (pinfunction "P$1_P$1") (pintype "bidirectional"))
    )
    (net (code "2") (name "5V") (class "Default")
      (node (ref "LIFE1TEMP") (pin "+") (pinfunction "+_+") (pintype "bidirectional"))
      (node (ref "LIFE3TEMP") (pin "+") (pinfunction "+_+") (pintype "bidirectional"))
      (node (ref "LION1TEMP") (pin "+") (pinfunction "+_+") (pintype "bidirectional"))
      (node (ref "LION2TEMP") (pin "+") (pinfunction "+_+") (pintype "bidirectional"))
      (node (ref "V9") (pin "P$1") (pinfunction "P$1_P$1") (pintype "bidirectional"))
    )
    (net (code "3") (name "GND") (class "Default")
      (node (ref "C1") (pin "2") (pinfunction "P$2_2") (pintype "passive"))
      (node (ref "C10") (pin "2") (pinfunction "P$2_2") (pintype "passive"))
      (node (ref "C11") (pin "2") (pinfunction "P$2_2") (pintype "passive"))
      (node (ref "C12") (pin "2") (pinfunction "P$2_2") (pintype "passive"))
      (node (ref "C13") (pin "1") (pinfunction "P$1_1") (pintype "passive"))
      (node (ref "C14") (pin "1") (pinfunction "P$1_1") (pintype "passive"))
      (node (ref "C15") (pin "1") (pinfunction "P$1_1") (pintype "passive"))
      (node (ref "C17") (pin "1") (pinfunction "P$1_1") (pintype "passive"))
      (node (ref "C18") (pin "2") (pinfunction "P$2_2") (pintype "passive"))
      (node (ref "C19") (pin "1") (pinfunction "P$1_1") (pintype "passive"))
      (node (ref "C2") (pin "2") (pinfunction "P$2_2") (pintype "passive"))
      (node (ref "C21") (pin "1") (pinfunction "P$1_1") (pintype "passive"))
      (node (ref "C22") (pin "2") (pinfunction "P$2_2") (pintype "passive"))
      (node (ref "C23") (pin "2") (pinfunction "P$2_2") (pintype "passive"))
      (node (ref "C24") (pin "2") (pinfunction "P$2_2") (pintype "passive"))
      (node (ref "C25") (pin "1") (pinfunction "P$1_1") (pintype "passive"))
      (node (ref "C26") (pin "2") (pinfunction "P$2_2") (pintype "passive"))
      (node (ref "C27") (pin "2") (pinfunction "P$2_2") (pintype "passive"))
      (node (ref "C28") (pin "1") (pinfunction "P$1_1") (pintype "passive"))
      (node (ref "C29") (pin "2") (pinfunction "P$2_2") (pintype "passive"))
      (node (ref "C3") (pin "2") (pinfunction "P$2_2") (pintype "passive"))
      (node (ref "C30") (pin "2") (pinfunction "P$2_2") (pintype "passive"))
      (node (ref "C6") (pin "2") (pinfunction "P$2_2") (pintype "passive"))
      (node (ref "C7") (pin "2") (pinfunction "P$2_2") (pintype "passive"))
      (node (ref "C8") (pin "2") (pinfunction "P$2_2") (pintype "passive"))
      (node (ref "C9") (pin "2") (pinfunction "P$2_2") (pintype "passive"))
      (node (ref "R14") (pin "1") (pinfunction "1_1") (pintype "passive"))
      (node (ref "R25") (pin "1") (pinfunction "1_1") (pintype "passive"))
      (node (ref "R26") (pin "1") (pinfunction "1_1") (pintype "passive"))
      (node (ref "R28") (pin "1") (pinfunction "1_1") (pintype "passive"))
      (node (ref "R29") (pin "1") (pinfunction "1_1") (pintype "passive"))
      (node (ref "R31") (pin "P$1") (pinfunction "1_P$1") (pintype "passive"))
      (node (ref "R32") (pin "P$1") (pinfunction "1_P$1") (pintype "passive"))
      (node (ref "R34") (pin "1") (pinfunction "1_1") (pintype "passive"))
      (node (ref "R36") (pin "1") (pinfunction "1_1") (pintype "passive"))
      (node (ref "R40") (pin "1") (pinfunction "1_1") (pintype "passive"))
      (node (ref "R41") (pin "P$1") (pinfunction "1_P$1") (pintype "passive"))
      (node (ref "R44") (pin "1") (pinfunction "1_1") (pintype "passive"))
      (node (ref "R46") (pin "1") (pinfunction "1_1") (pintype "passive"))
      (node (ref "R48") (pin "1") (pinfunction "1_1") (pintype "passive"))
      (node (ref "R50") (pin "1") (pinfunction "1_1") (pintype "passive"))
      (node (ref "R51") (pin "2") (pinfunction "2_2") (pintype "passive"))
      (node (ref "R56") (pin "1") (pinfunction "1_1") (pintype "passive"))
      (node (ref "R57") (pin "1") (pinfunction "1_1") (pintype "passive"))
      (node (ref "R58") (pin "1") (pinfunction "1_1") (pintype "passive"))
      (node (ref "R59") (pin "P$1") (pinfunction "1_P$1") (pintype "passive"))
      (node (ref "R62") (pin "1") (pinfunction "1_1") (pintype "passive"))
      (node (ref "R64") (pin "1") (pinfunction "1_1") (pintype "passive"))
      (node (ref "R66") (pin "1") (pinfunction "1_1") (pintype "passive"))
      (node (ref "R68") (pin "1") (pinfunction "1_1") (pintype "passive"))
      (node (ref "R69") (pin "2") (pinfunction "2_2") (pintype "passive"))
      (node (ref "R74") (pin "1") (pinfunction "1_1") (pintype "passive"))
      (node (ref "R75") (pin "1") (pinfunction "1_1") (pintype "passive"))
      (node (ref "R76") (pin "1") (pinfunction "1_1") (pintype "passive"))
      (node (ref "R77") (pin "1") (pinfunction "1_1") (pintype "passive"))
      (node (ref "R80") (pin "1") (pinfunction "1_1") (pintype "passive"))
      (node (ref "SW1") (pin "P$1") (pinfunction "GND_P$1") (pintype "bidirectional"))
      (node (ref "SW2") (pin "P$1") (pinfunction "GND_P$1") (pintype "bidirectional"))
      (node (ref "U$1") (pin "P$2") (pinfunction "GND_P$2") (pintype "bidirectional"))
      (node (ref "U$2") (pin "P$2") (pinfunction "GND_P$2") (pintype "bidirectional"))
      (node (ref "U$3") (pin "P$3") (pinfunction "S2_P$3") (pintype "bidirectional"))
      (node (ref "U$4") (pin "P$7") (pinfunction "GND_P$7") (pintype "bidirectional"))
      (node (ref "U$5") (pin "P$3") (pinfunction "S2_P$3") (pintype "bidirectional"))
      (node (ref "U$6") (pin "P$12") (pinfunction "GND_P$12") (pintype "power_in"))
      (node (ref "U$6") (pin "P$2") (pinfunction "A1_P$2") (pintype "bidirectional"))
      (node (ref "U$6") (pin "P$21") (pinfunction "A0_P$21") (pintype "bidirectional"))
      (node (ref "U$6") (pin "P$3") (pinfunction "A2_P$3") (pintype "bidirectional"))
      (node (ref "U1") (pin "P$2") (pinfunction "GND_P$2") (pintype "bidirectional"))
      (node (ref "U1") (pin "P$3") (pinfunction "CNTL_P$3") (pintype "bidirectional"))
      (node (ref "U3") (pin "P$12") (pinfunction "NTC_P$12") (pintype "bidirectional"))
      (node (ref "U3") (pin "P$17") (pinfunction "GND_P$17") (pintype "bidirectional"))
      (node (ref "U3") (pin "P$5") (pinfunction "GND_P$5") (pintype "bidirectional"))
      (node (ref "U3") (pin "P$7") (pinfunction "FREQ_P$7") (pintype "bidirectional"))
      (node (ref "U4") (pin "P$12") (pinfunction "NTC_P$12") (pintype "bidirectional"))
      (node (ref "U4") (pin "P$17") (pinfunction "GND_P$17") (pintype "bidirectional"))
      (node (ref "U4") (pin "P$5") (pinfunction "GND_P$5") (pintype "bidirectional"))
      (node (ref "U4") (pin "P$7") (pinfunction "FREQ_P$7") (pintype "bidirectional"))
      (node (ref "U5") (pin "P$12") (pinfunction "NTC_P$12") (pintype "bidirectional"))
      (node (ref "U5") (pin "P$17") (pinfunction "GND_P$17") (pintype "bidirectional"))
      (node (ref "U5") (pin "P$5") (pinfunction "GND_P$5") (pintype "bidirectional"))
      (node (ref "U5") (pin "P$7") (pinfunction "FREQ_P$7") (pintype "bidirectional"))
      (node (ref "U6") (pin "P$12") (pinfunction "NTC_P$12") (pintype "bidirectional"))
      (node (ref "U6") (pin "P$17") (pinfunction "GND_P$17") (pintype "bidirectional"))
      (node (ref "U6") (pin "P$5") (pinfunction "GND_P$5") (pintype "bidirectional"))
      (node (ref "U6") (pin "P$7") (pinfunction "FREQ_P$7") (pintype "bidirectional"))
      (node (ref "V12") (pin "P$1") (pinfunction "P$1_P$1") (pintype "bidirectional"))
      (node (ref "V13") (pin "P$1") (pinfunction "P$1_P$1") (pintype "bidirectional"))
      (node (ref "V22") (pin "P$1") (pinfunction "P$1_P$1") (pintype "bidirectional"))
      (node (ref "V23") (pin "P$1") (pinfunction "P$1_P$1") (pintype "bidirectional"))
    )
    (net (code "4") (name "L1_CHG") (class "Default")
      (node (ref "R15") (pin "2") (pinfunction "2_2") (pintype "passive"))
      (node (ref "U3") (pin "P$16") (pinfunction "RUN_P$16") (pintype "bidirectional"))
      (node (ref "V10") (pin "P$1") (pinfunction "P$1_P$1") (pintype "bidirectional"))
      (node (ref "V40") (pin "P$1") (pinfunction "P$1_P$1") (pintype "bidirectional"))
    )
    (net (code "5") (name "L1_CHGN") (class "Default")
      (node (ref "R17") (pin "1") (pinfunction "1_1") (pintype "passive"))
      (node (ref "U$6") (pin "P$8") (pinfunction "P04_P$8") (pintype "bidirectional"))
      (node (ref "U3") (pin "P$14") (pinfunction "~{CHRG}_P$14") (pintype "bidirectional"))
      (node (ref "V42") (pin "P$1") (pinfunction "P$1_P$1") (pintype "bidirectional"))
    )
    (net (code "6") (name "L1_DISG") (class "Default")
      (node (ref "U$1") (pin "P$3") (pinfunction "CNTRL_P$3") (pintype "bidirectional"))
      (node (ref "V34") (pin "P$1") (pinfunction "P$1_P$1") (pintype "bidirectional"))
      (node (ref "V46") (pin "P$1") (pinfunction "P$1_P$1") (pintype "bidirectional"))
    )
    (net (code "7") (name "L1_FAULTN") (class "Default")
      (node (ref "R18") (pin "1") (pinfunction "1_1") (pintype "passive"))
      (node (ref "U$6") (pin "P$9") (pinfunction "P05_P$9") (pintype "bidirectional"))
      (node (ref "U3") (pin "P$15") (pinfunction "~{FAULT}_P$15") (pintype "bidirectional"))
      (node (ref "V41") (pin "P$1") (pinfunction "P$1_P$1") (pintype "bidirectional"))
    )
    (net (code "8") (name "L1_REF") (class "Default")
      (node (ref "R33") (pin "1") (pinfunction "1_1") (pintype "passive"))
      (node (ref "R34") (pin "2") (pinfunction "2_2") (pintype "passive"))
      (node (ref "V25") (pin "P$1") (pinfunction "P$1_P$1") (pintype "bidirectional"))
      (node (ref "V44") (pin "P$1") (pinfunction "P$1_P$1") (pintype "bidirectional"))
    )
    (net (code "9") (name "L1_SNS") (class "Default")
      (node (ref "LI-ION1") (pin "MINUS") (pinfunction "MINUS_MINUS") (pintype "power_in"))
      (node (ref "R31") (pin "P$2") (pinfunction "2_P$2") (pintype "passive"))
      (node (ref "U$4") (pin "P$4") (pinfunction "VIN1_P$4") (pintype "bidirectional"))
      (node (ref "V43") (pin "P$1") (pinfunction "P$1_P$1") (pintype "bidirectional"))
    )
    (net (code "10") (name "L1_ST") (class "Default")
      (node (ref "R37") (pin "1") (pinfunction "1_1") (pintype "passive"))
      (node (ref "U$1") (pin "P$4") (pinfunction "STAT_P$4") (pintype "bidirectional"))
      (node (ref "U$6") (pin "P$5") (pinfunction "P01_P$5") (pintype "bidirectional"))
      (node (ref "V36") (pin "P$1") (pinfunction "P$1_P$1") (pintype "bidirectional"))
      (node (ref "V47") (pin "P$1") (pinfunction "P$1_P$1") (pintype "bidirectional"))
    )
    (net (code "11") (name "L1_TEMP") (class "Default")
      (node (ref "LION1TEMP") (pin "-") (pinfunction "-_-") (pintype "bidirectional"))
      (node (ref "V24") (pin "P$1") (pinfunction "P$1_P$1") (pintype "bidirectional"))
    )
    (net (code "12") (name "L2_CHG") (class "Default")
      (node (ref "R16") (pin "2") (pinfunction "2_2") (pintype "passive"))
      (node (ref "U4") (pin "P$16") (pinfunction "RUN_P$16") (pintype "bidirectional"))
      (node (ref "V33") (pin "P$1") (pinfunction "P$1_P$1") (pintype "bidirectional"))
    )
    (net (code "13") (name "L2_CHGN") (class "Default")
      (node (ref "R19") (pin "1") (pinfunction "1_1") (pintype "passive"))
      (node (ref "U$6") (pin "P$10") (pinfunction "P06_P$10") (pintype "bidirectional"))
      (node (ref "U4") (pin "P$14") (pinfunction "~{CHRG}_P$14") (pintype "bidirectional"))
    )
    (net (code "14") (name "L2_DISG") (class "Default")
      (node (ref "U$2") (pin "P$3") (pinfunction "CNTRL_P$3") (pintype "bidirectional"))
      (node (ref "V35") (pin "P$1") (pinfunction "P$1_P$1") (pintype "bidirectional"))
    )
    (net (code "15") (name "L2_FAULTN") (class "Default")
      (node (ref "R20") (pin "1") (pinfunction "1_1") (pintype "passive"))
      (node (ref "U$6") (pin "P$11") (pinfunction "P07_P$11") (pintype "bidirectional"))
      (node (ref "U4") (pin "P$15") (pinfunction "~{FAULT}_P$15") (pintype "bidirectional"))
    )
    (net (code "16") (name "L2_REF") (class "Default")
      (node (ref "R35") (pin "1") (pinfunction "1_1") (pintype "passive"))
      (node (ref "R36") (pin "2") (pinfunction "2_2") (pintype "passive"))
      (node (ref "V29") (pin "P$1") (pinfunction "P$1_P$1") (pintype "bidirectional"))
    )
    (net (code "17") (name "L2_SNS") (class "Default")
      (node (ref "LI-ION2") (pin "MINUS") (pinfunction "MINUS_MINUS") (pintype "power_in"))
      (node (ref "R32") (pin "P$2") (pinfunction "2_P$2") (pintype "passive"))
      (node (ref "U$4") (pin "P$3") (pinfunction "VIN0_P$3") (pintype "bidirectional"))
    )
    (net (code "18") (name "L2_ST") (class "Default")
      (node (ref "R38") (pin "1") (pinfunction "1_1") (pintype "passive"))
      (node (ref "U$2") (pin "P$4") (pinfunction "STAT_P$4") (pintype "bidirectional"))
      (node (ref "U$6") (pin "P$4") (pinfunction "P00_P$4") (pintype "bidirectional"))
      (node (ref "V38") (pin "P$1") (pinfunction "P$1_P$1") (pintype "bidirectional"))
    )
    (net (code "19") (name "L2_TEMP") (class "Default")
      (node (ref "LION2TEMP") (pin "-") (pinfunction "-_-") (pintype "bidirectional"))
      (node (ref "V32") (pin "P$1") (pinfunction "P$1_P$1") (pintype "bidirectional"))
    )
    (net (code "20") (name "LF1_REF") (class "Default")
      (node (ref "R49") (pin "2") (pinfunction "2_2") (pintype "passive"))
      (node (ref "R50") (pin "2") (pinfunction "2_2") (pintype "passive"))
      (node (ref "V58") (pin "P$1") (pinfunction "P$1_P$1") (pintype "bidirectional"))
    )
    (net (code "21") (name "LF1_TEMP") (class "Default")
      (node (ref "LIFE1TEMP") (pin "-") (pinfunction "-_-") (pintype "bidirectional"))
      (node (ref "V37") (pin "P$1") (pinfunction "P$1_P$1") (pintype "bidirectional"))
    )
    (net (code "22") (name "LF2_REF") (class "Default")
      (node (ref "R47") (pin "1") (pinfunction "1_1") (pintype "passive"))
      (node (ref "R48") (pin "2") (pinfunction "2_2") (pintype "passive"))
      (node (ref "V59") (pin "P$1") (pinfunction "P$1_P$1") (pintype "bidirectional"))
    )
    (net (code "23") (name "LF3_REF") (class "Default")
      (node (ref "R67") (pin "2") (pinfunction "2_2") (pintype "passive"))
      (node (ref "R68") (pin "2") (pinfunction "2_2") (pintype "passive"))
      (node (ref "V62") (pin "P$1") (pinfunction "P$1_P$1") (pintype "bidirectional"))
    )
    (net (code "24") (name "LF3_TEMP") (class "Default")
      (node (ref "LIFE3TEMP") (pin "-") (pinfunction "-_-") (pintype "bidirectional"))
      (node (ref "V50") (pin "P$1") (pinfunction "P$1_P$1") (pintype "bidirectional"))
    )
    (net (code "25") (name "LF4_REF") (class "Default")
      (node (ref "R65") (pin "1") (pinfunction "1_1") (pintype "passive"))
      (node (ref "R66") (pin "2") (pinfunction "2_2") (pintype "passive"))
      (node (ref "V61") (pin "P$1") (pinfunction "P$1_P$1") (pintype "bidirectional"))
    )
    (net (code "26") (name "LF_B1") (class "Default")
      (node (ref "C23") (pin "1") (pinfunction "P$1_1") (pintype "passive"))
      (node (ref "SW1") (pin "P$5") (pinfunction "OUT_P$5") (pintype "power_in"))
      (node (ref "SW1") (pin "P$6") (pinfunction "OUT_P$6") (pintype "power_in"))
      (node (ref "SW1") (pin "P$7") (pinfunction "OUT_P$7") (pintype "power_in"))
      (node (ref "V21") (pin "P$1") (pinfunction "P$1_P$1") (pintype "bidirectional"))
      (node (ref "V26") (pin "P$1") (pinfunction "P$1_P$1") (pintype "bidirectional"))
    )
    (net (code "27") (name "LF_B1_BT") (class "Default")
      (node (ref "R57") (pin "2") (pinfunction "2_2") (pintype "passive"))
      (node (ref "U$3") (pin "P$4") (pinfunction "G2_P$4") (pintype "bidirectional"))
      (node (ref "U$6") (pin "P$13") (pinfunction "P10_P$13") (pintype "bidirectional"))
    )
    (net (code "28") (name "LF_B1_CHG") (class "Default")
      (node (ref "R44") (pin "2") (pinfunction "2_2") (pintype "passive"))
      (node (ref "U5") (pin "P$16") (pinfunction "RUN_P$16") (pintype "bidirectional"))
      (node (ref "V15") (pin "P$1") (pinfunction "P$1_P$1") (pintype "bidirectional"))
    )
    (net (code "29") (name "LF_B1_CHGN") (class "Default")
      (node (ref "R42") (pin "1") (pinfunction "1_1") (pintype "passive"))
      (node (ref "U$6") (pin "P$19") (pinfunction "P16_P$19") (pintype "bidirectional"))
      (node (ref "U5") (pin "P$14") (pinfunction "~{CHRG}_P$14") (pintype "bidirectional"))
      (node (ref "V18") (pin "P$1") (pinfunction "P$1_P$1") (pintype "bidirectional"))
    )
    (net (code "30") (name "LF_B1_FAULTN") (class "Default")
      (node (ref "R43") (pin "1") (pinfunction "1_1") (pintype "passive"))
      (node (ref "U$6") (pin "P$20") (pinfunction "P17_P$20") (pintype "bidirectional"))
      (node (ref "U5") (pin "P$15") (pinfunction "~{FAULT}_P$15") (pintype "bidirectional"))
      (node (ref "V19") (pin "P$1") (pinfunction "P$1_P$1") (pintype "bidirectional"))
    )
    (net (code "31") (name "LF_B1_OSNS") (class "Default")
      (node (ref "C24") (pin "1") (pinfunction "P$1_1") (pintype "passive"))
      (node (ref "R79") (pin "1") (pinfunction "1_1") (pintype "passive"))
      (node (ref "V31") (pin "P$1") (pinfunction "P$1_P$1") (pintype "bidirectional"))
    )
    (net (code "32") (name "LF_B1_OUTEN") (class "Default")
      (node (ref "R78") (pin "1") (pinfunction "1_1") (pintype "passive"))
      (node (ref "V20") (pin "P$1") (pinfunction "P$1_P$1") (pintype "bidirectional"))
    )
    (net (code "34") (name "LF_B1_TT") (class "Default")
      (node (ref "R56") (pin "2") (pinfunction "2_2") (pintype "passive"))
      (node (ref "U$3") (pin "P$2") (pinfunction "G1_P$2") (pintype "bidirectional"))
      (node (ref "U$6") (pin "P$14") (pinfunction "P11_P$14") (pintype "bidirectional"))
    )
    (net (code "36") (name "LF_B2_BT") (class "Default")
      (node (ref "R75") (pin "2") (pinfunction "2_2") (pintype "passive"))
      (node (ref "U$5") (pin "P$4") (pinfunction "G2_P$4") (pintype "bidirectional"))
      (node (ref "U$6") (pin "P$16") (pinfunction "P13_P$16") (pintype "bidirectional"))
    )
    (net (code "37") (name "LF_B2_CHG") (class "Default")
      (node (ref "R62") (pin "2") (pinfunction "2_2") (pintype "passive"))
      (node (ref "U6") (pin "P$16") (pinfunction "RUN_P$16") (pintype "bidirectional"))
      (node (ref "V57") (pin "P$1") (pinfunction "P$1_P$1") (pintype "bidirectional"))
    )
    (net (code "38") (name "LF_B2_CHGN") (class "Default")
      (node (ref "R60") (pin "1") (pinfunction "1_1") (pintype "passive"))
      (node (ref "U$6") (pin "P$17") (pinfunction "P14_P$17") (pintype "bidirectional"))
      (node (ref "U6") (pin "P$14") (pinfunction "~{CHRG}_P$14") (pintype "bidirectional"))
    )
    (net (code "39") (name "LF_B2_FAULTN") (class "Default")
      (node (ref "R61") (pin "1") (pinfunction "1_1") (pintype "passive"))
      (node (ref "U$6") (pin "P$18") (pinfunction "P15_P$18") (pintype "bidirectional"))
      (node (ref "U6") (pin "P$15") (pinfunction "~{FAULT}_P$15") (pintype "bidirectional"))
    )
    (net (code "40") (name "LF_B2_OSNS") (class "Default")
      (node (ref "C27") (pin "1") (pinfunction "P$1_1") (pintype "passive"))
      (node (ref "R82") (pin "1") (pinfunction "1_1") (pintype "passive"))
      (node (ref "V63") (pin "P$1") (pinfunction "P$1_P$1") (pintype "bidirectional"))
    )
    (net (code "41") (name "LF_B2_OUTEN") (class "Default")
      (node (ref "R81") (pin "1") (pinfunction "1_1") (pintype "passive"))
      (node (ref "V56") (pin "P$1") (pinfunction "P$1_P$1") (pintype "bidirectional"))
    )
    (net (code "42") (name "LF_B2_SNS") (class "Default")
      (node (ref "LIFEPO4") (pin "MINUS") (pinfunction "MINUS_MINUS") (pintype "power_in"))
      (node (ref "R59") (pin "P$2") (pinfunction "2_P$2") (pintype "passive"))
      (node (ref "V60") (pin "P$1") (pinfunction "P$1_P$1") (pintype "bidirectional"))
    )
    (net (code "43") (name "LF_B2_TT") (class "Default")
      (node (ref "R74") (pin "2") (pinfunction "2_2") (pintype "passive"))
      (node (ref "U$5") (pin "P$2") (pinfunction "G1_P$2") (pintype "bidirectional"))
      (node (ref "U$6") (pin "P$15") (pinfunction "P12_P$15") (pintype "bidirectional"))
    )
    (net (code "44") (name "LIFE1") (class "Default")
      (node (ref "C18") (pin "1") (pinfunction "P$1_1") (pintype "passive"))
      (node (ref "LIFEPO1") (pin "PLUS") (pinfunction "PLUS_PLUS") (pintype "power_in"))
      (node (ref "R49") (pin "1") (pinfunction "1_1") (pintype "passive"))
      (node (ref "R53") (pin "2") (pinfunction "2_2") (pintype "passive"))
      (node (ref "R54") (pin "P$2") (pinfunction "2_P$2") (pintype "passive"))
      (node (ref "SW1") (pin "PAD") (pinfunction "VB_PAD") (pintype "power_in"))
      (node (ref "U5") (pin "P$9") (pinfunction "BAT_P$9") (pintype "bidirectional"))
      (node (ref "V17") (pin "P$1") (pinfunction "P$1_P$1") (pintype "bidirectional"))
    )
    (net (code "45") (name "LIFE3") (class "Default")
      (node (ref "C22") (pin "1") (pinfunction "P$1_1") (pintype "passive"))
      (node (ref "LIFEPO3") (pin "PLUS") (pinfunction "PLUS_PLUS") (pintype "power_in"))
      (node (ref "R67") (pin "1") (pinfunction "1_1") (pintype "passive"))
      (node (ref "R71") (pin "2") (pinfunction "2_2") (pintype "passive"))
      (node (ref "R72") (pin "P$2") (pinfunction "2_P$2") (pintype "passive"))
      (node (ref "SW2") (pin "PAD") (pinfunction "VB_PAD") (pintype "power_in"))
      (node (ref "U6") (pin "P$9") (pinfunction "BAT_P$9") (pintype "bidirectional"))
    )
    (net (code "46") (name "LIFEB1SNS") (class "Default")
      (node (ref "LIFEPO2") (pin "MINUS") (pinfunction "MINUS_MINUS") (pintype "power_in"))
      (node (ref "R41") (pin "P$2") (pinfunction "2_P$2") (pintype "passive"))
      (node (ref "V14") (pin "P$1") (pinfunction "P$1_P$1") (pintype "bidirectional"))
    )
    (net (code "47") (name "LIFE_B2") (class "Default")
      (node (ref "C26") (pin "1") (pinfunction "P$1_1") (pintype "passive"))
      (node (ref "SW2") (pin "P$5") (pinfunction "OUT_P$5") (pintype "power_in"))
      (node (ref "SW2") (pin "P$6") (pinfunction "OUT_P$6") (pintype "power_in"))
      (node (ref "SW2") (pin "P$7") (pinfunction "OUT_P$7") (pintype "power_in"))
      (node (ref "V27") (pin "P$1") (pinfunction "P$1_P$1") (pintype "bidirectional"))
      (node (ref "V28") (pin "P$1") (pinfunction "P$1_P$1") (pintype "bidirectional"))
    )
    (net (code "48") (name "LION1") (class "Default")
      (node (ref "C13") (pin "2") (pinfunction "P$2_2") (pintype "passive"))
      (node (ref "C8") (pin "1") (pinfunction "P$1_1") (pintype "passive"))
      (node (ref "LI-ION1") (pin "PLUS") (pinfunction "PLUS_PLUS") (pintype "power_in"))
      (node (ref "R21") (pin "2") (pinfunction "2_2") (pintype "passive"))
      (node (ref "R33") (pin "2") (pinfunction "2_2") (pintype "passive"))
      (node (ref "U$1") (pin "P$1") (pinfunction "IN_P$1") (pintype "bidirectional"))
      (node (ref "U3") (pin "P$9") (pinfunction "BAT_P$9") (pintype "bidirectional"))
      (node (ref "V45") (pin "P$1") (pinfunction "P$1_P$1") (pintype "bidirectional"))
    )
    (net (code "49") (name "LION2") (class "Default")
      (node (ref "C14") (pin "2") (pinfunction "P$2_2") (pintype "passive"))
      (node (ref "C9") (pin "1") (pinfunction "P$1_1") (pintype "passive"))
      (node (ref "LI-ION2") (pin "PLUS") (pinfunction "PLUS_PLUS") (pintype "power_in"))
      (node (ref "R24") (pin "2") (pinfunction "2_2") (pintype "passive"))
      (node (ref "R35") (pin "2") (pinfunction "2_2") (pintype "passive"))
      (node (ref "U$2") (pin "P$1") (pinfunction "IN_P$1") (pintype "bidirectional"))
      (node (ref "U4") (pin "P$9") (pinfunction "BAT_P$9") (pintype "bidirectional"))
    )
    (net (code "50") (name "L_OUT") (class "Default")
      (node (ref "C11") (pin "1") (pinfunction "P$1_1") (pintype "passive"))
      (node (ref "C12") (pin "1") (pinfunction "P$1_1") (pintype "passive"))
      (node (ref "R37") (pin "2") (pinfunction "2_2") (pintype "passive"))
      (node (ref "R38") (pin "2") (pinfunction "2_2") (pintype "passive"))
      (node (ref "R39") (pin "2") (pinfunction "2_2") (pintype "passive"))
      (node (ref "U$1") (pin "P$5") (pinfunction "OUT_P$5") (pintype "bidirectional"))
      (node (ref "U$2") (pin "P$5") (pinfunction "OUT_P$5") (pintype "bidirectional"))
      (node (ref "V30") (pin "P$1") (pinfunction "P$1_P$1") (pintype "bidirectional"))
      (node (ref "V48") (pin "P$1") (pinfunction "P$1_P$1") (pintype "bidirectional"))
      (node (ref "V54") (pin "P$1") (pinfunction "P$1_P$1") (pintype "bidirectional"))
    )
    (net (code "51") (name "L_REF") (class "Default")
      (node (ref "R39") (pin "1") (pinfunction "1_1") (pintype "passive"))
      (node (ref "R40") (pin "2") (pinfunction "2_2") (pintype "passive"))
      (node (ref "U$4") (pin "P$5") (pinfunction "VIN2_P$5") (pintype "bidirectional"))
    )
    (net (code "52") (name "Net-(C1-P$1)") (class "Default")
      (node (ref "C1") (pin "1") (pinfunction "P$1_1") (pintype "passive"))
      (node (ref "M1") (pin "P$5") (pinfunction "D_P$5") (pintype "bidirectional"))
      (node (ref "M1") (pin "P$6") (pinfunction "D_P$6") (pintype "bidirectional"))
      (node (ref "M1") (pin "P$7") (pinfunction "D_P$7") (pintype "bidirectional"))
      (node (ref "M1") (pin "P$8") (pinfunction "D_P$8") (pintype "bidirectional"))
      (node (ref "R2") (pin "2") (pinfunction "2_2") (pintype "passive"))
      (node (ref "U1") (pin "P$1") (pinfunction "VIN_P$1") (pintype "bidirectional"))
    )
    (net (code "53") (name "Net-(C2-P$1)") (class "Default")
      (node (ref "C2") (pin "1") (pinfunction "P$1_1") (pintype "passive"))
      (node (ref "M1") (pin "P$1") (pinfunction "S_P$1") (pintype "bidirectional"))
      (node (ref "M1") (pin "P$2") (pinfunction "S_P$2") (pintype "bidirectional"))
      (node (ref "M1") (pin "P$3") (pinfunction "S_P$3") (pintype "bidirectional"))
      (node (ref "R4") (pin "1") (pinfunction "1_1") (pintype "passive"))
      (node (ref "U1") (pin "P$6") (pinfunction "SNS_P$6") (pintype "bidirectional"))
    )
    (net (code "54") (name "Net-(C4-P$1)") (class "Default")
      (node (ref "C4") (pin "1") (pinfunction "P$1_1") (pintype "passive"))
      (node (ref "U3") (pin "P$2") (pinfunction "BOOST_P$2") (pintype "bidirectional"))
    )
    (net (code "55") (name "Net-(C4-P$2)") (class "Default")
      (node (ref "C4") (pin "2") (pinfunction "P$2_2") (pintype "passive"))
      (node (ref "L1") (pin "P$1") (pinfunction "P$1_P$1") (pintype "passive"))
      (node (ref "U3") (pin "P$4") (pinfunction "SW_P$4") (pintype "bidirectional"))
    )
    (net (code "56") (name "Net-(C5-P$1)") (class "Default")
      (node (ref "C5") (pin "1") (pinfunction "P$1_1") (pintype "passive"))
      (node (ref "U4") (pin "P$2") (pinfunction "BOOST_P$2") (pintype "bidirectional"))
    )
    (net (code "57") (name "Net-(C5-P$2)") (class "Default")
      (node (ref "C5") (pin "2") (pinfunction "P$2_2") (pintype "passive"))
      (node (ref "L2") (pin "P$1") (pinfunction "P$1_P$1") (pintype "passive"))
      (node (ref "U4") (pin "P$4") (pinfunction "SW_P$4") (pintype "bidirectional"))
    )
    (net (code "58") (name "Net-(C6-P$1)") (class "Default")
      (node (ref "C6") (pin "1") (pinfunction "P$1_1") (pintype "passive"))
      (node (ref "U3") (pin "P$1") (pinfunction "INTVCC_P$1") (pintype "bidirectional"))
    )
    (net (code "59") (name "Net-(C7-P$1)") (class "Default")
      (node (ref "C7") (pin "1") (pinfunction "P$1_1") (pintype "passive"))
      (node (ref "U4") (pin "P$1") (pinfunction "INTVCC_P$1") (pintype "bidirectional"))
    )
    (net (code "60") (name "Net-(C15-P$2)") (class "Default")
      (node (ref "C15") (pin "2") (pinfunction "P$2_2") (pintype "passive"))
      (node (ref "U5") (pin "P$1") (pinfunction "INTVCC_P$1") (pintype "bidirectional"))
    )
    (net (code "61") (name "Net-(C16-P$1)") (class "Default")
      (node (ref "C16") (pin "1") (pinfunction "P$1_1") (pintype "passive"))
      (node (ref "L3") (pin "P$2") (pinfunction "P$2_P$2") (pintype "passive"))
      (node (ref "U5") (pin "P$4") (pinfunction "SW_P$4") (pintype "bidirectional"))
    )
    (net (code "62") (name "Net-(C16-P$2)") (class "Default")
      (node (ref "C16") (pin "2") (pinfunction "P$2_2") (pintype "passive"))
      (node (ref "U5") (pin "P$2") (pinfunction "BOOST_P$2") (pintype "bidirectional"))
    )
    (net (code "63") (name "Net-(C19-P$2)") (class "Default")
      (node (ref "C19") (pin "2") (pinfunction "P$2_2") (pintype "passive"))
      (node (ref "U6") (pin "P$1") (pinfunction "INTVCC_P$1") (pintype "bidirectional"))
    )
    (net (code "64") (name "Net-(C20-P$1)") (class "Default")
      (node (ref "C20") (pin "1") (pinfunction "P$1_1") (pintype "passive"))
      (node (ref "L4") (pin "P$2") (pinfunction "P$2_P$2") (pintype "passive"))
      (node (ref "U6") (pin "P$4") (pinfunction "SW_P$4") (pintype "bidirectional"))
    )
    (net (code "65") (name "Net-(C20-P$2)") (class "Default")
      (node (ref "C20") (pin "2") (pinfunction "P$2_2") (pintype "passive"))
      (node (ref "U6") (pin "P$2") (pinfunction "BOOST_P$2") (pintype "bidirectional"))
    )
    (net (code "66") (name "Net-(C25-P$2)") (class "Default")
      (node (ref "C25") (pin "2") (pinfunction "P$2_2") (pintype "passive"))
      (node (ref "R77") (pin "2") (pinfunction "2_2") (pintype "passive"))
      (node (ref "R78") (pin "2") (pinfunction "2_2") (pintype "passive"))
      (node (ref "SW1") (pin "P$2") (pinfunction "CNTRL_P$2") (pintype "input"))
    )
    (net (code "67") (name "Net-(C28-P$2)") (class "Default")
      (node (ref "C28") (pin "2") (pinfunction "P$2_2") (pintype "passive"))
      (node (ref "R80") (pin "2") (pinfunction "2_2") (pintype "passive"))
      (node (ref "R81") (pin "2") (pinfunction "2_2") (pintype "passive"))
      (node (ref "SW2") (pin "P$2") (pinfunction "CNTRL_P$2") (pintype "input"))
    )
    (net (code "68") (name "Net-(D7-PadA)") (class "Default")
      (node (ref "D7") (pin "A") (pinfunction "A_A") (pintype "bidirectional"))
      (node (ref "R1") (pin "2") (pinfunction "2_2") (pintype "passive"))
    )
    (net (code "69") (name "Net-(D7-PadC)") (class "Default")
      (node (ref "D7") (pin "C") (pinfunction "C_C") (pintype "bidirectional"))
      (node (ref "R3") (pin "1") (pinfunction "1_1") (pintype "passive"))
    )
    (net (code "70") (name "Net-(M1-G)") (class "Default")
      (node (ref "M1") (pin "P$4") (pinfunction "G_P$4") (pintype "bidirectional"))
      (node (ref "U1") (pin "P$5") (pinfunction "GATE_P$5") (pintype "bidirectional"))
    )
    (net (code "71") (name "Net-(R54-1)") (class "Default")
      (node (ref "R54") (pin "P$1") (pinfunction "1_P$1") (pintype "passive"))
      (node (ref "U$3") (pin "P$7") (pinfunction "D1_P$7") (pintype "bidirectional"))
      (node (ref "U$3") (pin "P$8") (pinfunction "D1_P$8") (pintype "bidirectional"))
    )
    (net (code "72") (name "Net-(R55-1)") (class "Default")
      (node (ref "LIFEPO1") (pin "MINUS") (pinfunction "MINUS_MINUS") (pintype "power_in"))
      (node (ref "LIFEPO2") (pin "PLUS") (pinfunction "PLUS_PLUS") (pintype "power_in"))
      (node (ref "R47") (pin "2") (pinfunction "2_2") (pintype "passive"))
      (node (ref "R55") (pin "P$1") (pinfunction "1_P$1") (pintype "passive"))
      (node (ref "U$3") (pin "P$1") (pinfunction "S1_P$1") (pintype "bidirectional"))
      (node (ref "V16") (pin "P$1") (pinfunction "P$1_P$1") (pintype "bidirectional"))
    )
    (net (code "73") (name "Net-(R55-2)") (class "Default")
      (node (ref "R55") (pin "P$2") (pinfunction "2_P$2") (pintype "passive"))
      (node (ref "U$3") (pin "P$5") (pinfunction "D2_P$5") (pintype "bidirectional"))
      (node (ref "U$3") (pin "P$6") (pinfunction "D2_P$6") (pintype "bidirectional"))
    )
    (net (code "74") (name "Net-(R72-1)") (class "Default")
      (node (ref "R72") (pin "P$1") (pinfunction "1_P$1") (pintype "passive"))
      (node (ref "U$5") (pin "P$7") (pinfunction "D1_P$7") (pintype "bidirectional"))
      (node (ref "U$5") (pin "P$8") (pinfunction "D1_P$8") (pintype "bidirectional"))
    )
    (net (code "75") (name "Net-(R73-1)") (class "Default")
      (node (ref "LIFEPO3") (pin "MINUS") (pinfunction "MINUS_MINUS") (pintype "power_in"))
      (node (ref "LIFEPO4") (pin "PLUS") (pinfunction "PLUS_PLUS") (pintype "power_in"))
      (node (ref "R65") (pin "2") (pinfunction "2_2") (pintype "passive"))
      (node (ref "R73") (pin "P$1") (pinfunction "1_P$1") (pintype "passive"))
      (node (ref "U$5") (pin "P$1") (pinfunction "S1_P$1") (pintype "bidirectional"))
    )
    (net (code "76") (name "Net-(R73-2)") (class "Default")
      (node (ref "R73") (pin "P$2") (pinfunction "2_P$2") (pintype "passive"))
      (node (ref "U$5") (pin "P$5") (pinfunction "D2_P$5") (pintype "bidirectional"))
      (node (ref "U$5") (pin "P$6") (pinfunction "D2_P$6") (pintype "bidirectional"))
    )
    (net (code "77") (name "Net-(SW1-ISNS)") (class "Default")
      (node (ref "R58") (pin "2") (pinfunction "2_2") (pintype "passive"))
      (node (ref "R79") (pin "2") (pinfunction "2_2") (pintype "passive"))
      (node (ref "SW1") (pin "P$3") (pinfunction "ISNS_P$3") (pintype "output"))
    )
    (net (code "78") (name "Net-(SW2-ISNS)") (class "Default")
      (node (ref "R76") (pin "2") (pinfunction "2_2") (pintype "passive"))
      (node (ref "R82") (pin "2") (pinfunction "2_2") (pintype "passive"))
      (node (ref "SW2") (pin "P$3") (pinfunction "ISNS_P$3") (pintype "output"))
    )
    (net (code "79") (name "Net-(U3-CHGSNS)") (class "Default")
      (node (ref "L1") (pin "P$2") (pinfunction "P$2_P$2") (pintype "passive"))
      (node (ref "U3") (pin "P$8") (pinfunction "CHGSNS_P$8") (pintype "bidirectional"))
    )
    (net (code "80") (name "Net-(U3-FB)") (class "Default")
      (node (ref "R21") (pin "1") (pinfunction "1_1") (pintype "passive"))
      (node (ref "R22") (pin "2") (pinfunction "2_2") (pintype "passive"))
      (node (ref "U3") (pin "P$10") (pinfunction "FB_P$10") (pintype "bidirectional"))
    )
    (net (code "81") (name "Net-(U3-FBG)") (class "Default")
      (node (ref "R22") (pin "1") (pinfunction "1_1") (pintype "passive"))
      (node (ref "U3") (pin "P$11") (pinfunction "FBG_P$11") (pintype "bidirectional"))
    )
    (net (code "82") (name "Net-(U3-MPPT)") (class "Default")
      (node (ref "R27") (pin "1") (pinfunction "1_1") (pintype "passive"))
      (node (ref "R28") (pin "2") (pinfunction "2_2") (pintype "passive"))
      (node (ref "U3") (pin "P$6") (pinfunction "MPPT_P$6") (pintype "bidirectional"))
    )
    (net (code "83") (name "Net-(U3-PROG)") (class "Default")
      (node (ref "R25") (pin "2") (pinfunction "2_2") (pintype "passive"))
      (node (ref "U3") (pin "P$13") (pinfunction "PROG_P$13") (pintype "bidirectional"))
    )
    (net (code "84") (name "Net-(U4-CHGSNS)") (class "Default")
      (node (ref "L2") (pin "P$2") (pinfunction "P$2_P$2") (pintype "passive"))
      (node (ref "U4") (pin "P$8") (pinfunction "CHGSNS_P$8") (pintype "bidirectional"))
    )
    (net (code "85") (name "Net-(U4-FB)") (class "Default")
      (node (ref "R23") (pin "2") (pinfunction "2_2") (pintype "passive"))
      (node (ref "R24") (pin "1") (pinfunction "1_1") (pintype "passive"))
      (node (ref "U4") (pin "P$10") (pinfunction "FB_P$10") (pintype "bidirectional"))
    )
    (net (code "86") (name "Net-(U4-FBG)") (class "Default")
      (node (ref "R23") (pin "1") (pinfunction "1_1") (pintype "passive"))
      (node (ref "U4") (pin "P$11") (pinfunction "FBG_P$11") (pintype "bidirectional"))
    )
    (net (code "87") (name "Net-(U4-MPPT)") (class "Default")
      (node (ref "R29") (pin "2") (pinfunction "2_2") (pintype "passive"))
      (node (ref "R30") (pin "1") (pinfunction "1_1") (pintype "passive"))
      (node (ref "U4") (pin "P$6") (pinfunction "MPPT_P$6") (pintype "bidirectional"))
    )
    (net (code "88") (name "Net-(U4-PROG)") (class "Default")
      (node (ref "R26") (pin "2") (pinfunction "2_2") (pintype "passive"))
      (node (ref "U4") (pin "P$13") (pinfunction "PROG_P$13") (pintype "bidirectional"))
    )
    (net (code "89") (name "Net-(U5-CHGSNS)") (class "Default")
      (node (ref "L3") (pin "P$1") (pinfunction "P$1_P$1") (pintype "passive"))
      (node (ref "U5") (pin "P$8") (pinfunction "CHGSNS_P$8") (pintype "bidirectional"))
    )
    (net (code "90") (name "Net-(U5-FB)") (class "Default")
      (node (ref "R52") (pin "2") (pinfunction "2_2") (pintype "passive"))
      (node (ref "R53") (pin "1") (pinfunction "1_1") (pintype "passive"))
      (node (ref "U5") (pin "P$10") (pinfunction "FB_P$10") (pintype "bidirectional"))
    )
    (net (code "91") (name "Net-(U5-FBG)") (class "Default")
      (node (ref "R52") (pin "1") (pinfunction "1_1") (pintype "passive"))
      (node (ref "U5") (pin "P$11") (pinfunction "FBG_P$11") (pintype "bidirectional"))
    )
    (net (code "92") (name "Net-(U5-MPPT)") (class "Default")
      (node (ref "R45") (pin "1") (pinfunction "1_1") (pintype "passive"))
      (node (ref "R46") (pin "2") (pinfunction "2_2") (pintype "passive"))
      (node (ref "U5") (pin "P$6") (pinfunction "MPPT_P$6") (pintype "bidirectional"))
    )
    (net (code "93") (name "Net-(U5-PROG)") (class "Default")
      (node (ref "R51") (pin "1") (pinfunction "1_1") (pintype "passive"))
      (node (ref "U5") (pin "P$13") (pinfunction "PROG_P$13") (pintype "bidirectional"))
    )
    (net (code "94") (name "Net-(U6-CHGSNS)") (class "Default")
      (node (ref "L4") (pin "P$1") (pinfunction "P$1_P$1") (pintype "passive"))
      (node (ref "U6") (pin "P$8") (pinfunction "CHGSNS_P$8") (pintype "bidirectional"))
    )
    (net (code "95") (name "Net-(U6-FB)") (class "Default")
      (node (ref "R70") (pin "2") (pinfunction "2_2") (pintype "passive"))
      (node (ref "R71") (pin "1") (pinfunction "1_1") (pintype "passive"))
      (node (ref "U6") (pin "P$10") (pinfunction "FB_P$10") (pintype "bidirectional"))
    )
    (net (code "96") (name "Net-(U6-FBG)") (class "Default")
      (node (ref "R70") (pin "1") (pinfunction "1_1") (pintype "passive"))
      (node (ref "U6") (pin "P$11") (pinfunction "FBG_P$11") (pintype "bidirectional"))
    )
    (net (code "97") (name "Net-(U6-MPPT)") (class "Default")
      (node (ref "R63") (pin "1") (pinfunction "1_1") (pintype "passive"))
      (node (ref "R64") (pin "2") (pinfunction "2_2") (pintype "passive"))
      (node (ref "U6") (pin "P$6") (pinfunction "MPPT_P$6") (pintype "bidirectional"))
    )
    (net (code "98") (name "Net-(U6-PROG)") (class "Default")
      (node (ref "R69") (pin "1") (pinfunction "1_1") (pintype "passive"))
      (node (ref "U6") (pin "P$13") (pinfunction "PROG_P$13") (pintype "bidirectional"))
    )
    (net (code "99") (name "PANELREF") (class "Default")
      (node (ref "R13") (pin "1") (pinfunction "1_1") (pintype "passive"))
      (node (ref "R14") (pin "2") (pinfunction "2_2") (pintype "passive"))
      (node (ref "U$4") (pin "P$6") (pinfunction "VIN3/REF_P$6") (pintype "bidirectional"))
    )
    (net (code "100") (name "SCL") (class "Default")
      (node (ref "R85") (pin "1") (pinfunction "1_1") (pintype "passive"))
      (node (ref "U$4") (pin "P$1") (pinfunction "SCL_P$1") (pintype "bidirectional"))
      (node (ref "U$6") (pin "P$22") (pinfunction "SCL_P$22") (pintype "bidirectional"))
      (node (ref "V52") (pin "P$1") (pinfunction "P$1_P$1") (pintype "bidirectional"))
    )
    (net (code "101") (name "SDA") (class "Default")
      (node (ref "R86") (pin "1") (pinfunction "1_1") (pintype "passive"))
      (node (ref "U$4") (pin "P$2") (pinfunction "SDA_P$2") (pintype "bidirectional"))
      (node (ref "U$6") (pin "P$23") (pinfunction "SDA_P$23") (pintype "bidirectional"))
      (node (ref "V53") (pin "P$1") (pinfunction "P$1_P$1") (pintype "bidirectional"))
    )
    (net (code "102") (name "SPF_ST") (class "Default")
      (node (ref "R83") (pin "1") (pinfunction "1_1") (pintype "passive"))
      (node (ref "U$6") (pin "P$6") (pinfunction "P02_P$6") (pintype "bidirectional"))
      (node (ref "U1") (pin "P$4") (pinfunction "STAT_P$4") (pintype "bidirectional"))
    )
    (net (code "103") (name "SP_C") (class "Default")
      (node (ref "D1") (pin "C") (pinfunction "C_C") (pintype "bidirectional"))
      (node (ref "D2") (pin "C") (pinfunction "C_C") (pintype "bidirectional"))
      (node (ref "D3") (pin "C") (pinfunction "C_C") (pintype "bidirectional"))
      (node (ref "D4") (pin "C") (pinfunction "C_C") (pintype "bidirectional"))
      (node (ref "D5") (pin "C") (pinfunction "C_C") (pintype "bidirectional"))
      (node (ref "R1") (pin "1") (pinfunction "1_1") (pintype "passive"))
      (node (ref "R10") (pin "2") (pinfunction "2_2") (pintype "passive"))
      (node (ref "R2") (pin "1") (pinfunction "1_1") (pintype "passive"))
      (node (ref "R5") (pin "1") (pinfunction "1_1") (pintype "passive"))
      (node (ref "R6") (pin "2") (pinfunction "2_2") (pintype "passive"))
      (node (ref "R7") (pin "2") (pinfunction "2_2") (pintype "passive"))
      (node (ref "R8") (pin "2") (pinfunction "2_2") (pintype "passive"))
      (node (ref "R9") (pin "2") (pinfunction "2_2") (pintype "passive"))
    )
    (net (code "104") (name "SP_C_O") (class "Default")
      (node (ref "R11") (pin "1") (pinfunction "1_1") (pintype "passive"))
      (node (ref "R12") (pin "1") (pinfunction "1_1") (pintype "passive"))
      (node (ref "R3") (pin "2") (pinfunction "2_2") (pintype "passive"))
      (node (ref "R4") (pin "2") (pinfunction "2_2") (pintype "passive"))
      (node (ref "R5") (pin "2") (pinfunction "2_2") (pintype "passive"))
      (node (ref "V7") (pin "P$1") (pinfunction "P$1_P$1") (pintype "bidirectional"))
    )
    (net (code "105") (name "SP_OUT") (class "Default")
      (node (ref "C10") (pin "1") (pinfunction "P$1_1") (pintype "passive"))
      (node (ref "C17") (pin "2") (pinfunction "P$2_2") (pintype "passive"))
      (node (ref "C21") (pin "2") (pinfunction "P$2_2") (pintype "passive"))
      (node (ref "C3") (pin "1") (pinfunction "P$1_1") (pintype "passive"))
      (node (ref "D6") (pin "C") (pinfunction "C_C") (pintype "bidirectional"))
      (node (ref "R11") (pin "2") (pinfunction "2_2") (pintype "passive"))
      (node (ref "R12") (pin "2") (pinfunction "2_2") (pintype "passive"))
      (node (ref "R13") (pin "2") (pinfunction "2_2") (pintype "passive"))
      (node (ref "R15") (pin "1") (pinfunction "1_1") (pintype "passive"))
      (node (ref "R16") (pin "1") (pinfunction "1_1") (pintype "passive"))
      (node (ref "R27") (pin "2") (pinfunction "2_2") (pintype "passive"))
      (node (ref "R30") (pin "2") (pinfunction "2_2") (pintype "passive"))
      (node (ref "R45") (pin "2") (pinfunction "2_2") (pintype "passive"))
      (node (ref "R63") (pin "2") (pinfunction "2_2") (pintype "passive"))
      (node (ref "U3") (pin "P$3") (pinfunction "IN_P$3") (pintype "bidirectional"))
      (node (ref "U4") (pin "P$3") (pinfunction "IN_P$3") (pintype "bidirectional"))
      (node (ref "U5") (pin "P$3") (pinfunction "IN_P$3") (pintype "bidirectional"))
      (node (ref "U6") (pin "P$3") (pinfunction "IN_P$3") (pintype "bidirectional"))
      (node (ref "V8") (pin "P$1") (pinfunction "P$1_P$1") (pintype "bidirectional"))
    )
    (net (code "106") (name "UMB_CHG") (class "Default")
      (node (ref "D6") (pin "A") (pinfunction "A_A") (pintype "bidirectional"))
      (node (ref "V1") (pin "P$1") (pinfunction "P$1_P$1") (pintype "bidirectional"))
      (node (ref "V39") (pin "P$1") (pinfunction "P$1_P$1") (pintype "bidirectional"))
    )
    (net (code "107") (name "X_N") (class "Default")
      (node (ref "D2") (pin "A") (pinfunction "A_A") (pintype "bidirectional"))
      (node (ref "R7") (pin "1") (pinfunction "1_1") (pintype "passive"))
      (node (ref "V3") (pin "P$1") (pinfunction "P$1_P$1") (pintype "bidirectional"))
    )
    (net (code "108") (name "X_P") (class "Default")
      (node (ref "D1") (pin "A") (pinfunction "A_A") (pintype "bidirectional"))
      (node (ref "R6") (pin "1") (pinfunction "1_1") (pintype "passive"))
      (node (ref "V2") (pin "P$1") (pinfunction "P$1_P$1") (pintype "bidirectional"))
      (node (ref "V49") (pin "P$1") (pinfunction "P$1_P$1") (pintype "bidirectional"))
    )
    (net (code "109") (name "Y_N") (class "Default")
      (node (ref "D5") (pin "A") (pinfunction "A_A") (pintype "bidirectional"))
      (node (ref "R10") (pin "1") (pinfunction "1_1") (pintype "passive"))
      (node (ref "V6") (pin "P$1") (pinfunction "P$1_P$1") (pintype "bidirectional"))
    )
    (net (code "110") (name "Z_N") (class "Default")
      (node (ref "D4") (pin "A") (pinfunction "A_A") (pintype "bidirectional"))
      (node (ref "R9") (pin "1") (pinfunction "1_1") (pintype "passive"))
      (node (ref "V5") (pin "P$1") (pinfunction "P$1_P$1") (pintype "bidirectional"))
    )
    (net (code "111") (name "Z_P") (class "Default")
      (node (ref "D3") (pin "A") (pinfunction "A_A") (pintype "bidirectional"))
      (node (ref "R8") (pin "1") (pinfunction "1_1") (pintype "passive"))
      (node (ref "V4") (pin "P$1") (pinfunction "P$1_P$1") (pintype "bidirectional"))
    )
    (net (code "112") (name "unconnected-(U$6-P03-PadP$7)") (class "Default")
      (node (ref "U$6") (pin "P$7") (pinfunction "P03_P$7") (pintype "bidirectional"))
    )
    (net (code "113") (name "~{BATT_INT}") (class "Default")
      (node (ref "R84") (pin "1") (pinfunction "1_1") (pintype "passive"))
      (node (ref "U$6") (pin "P$1") (pinfunction "~{INT}_P$1") (pintype "bidirectional"))
      (node (ref "V11") (pin "P$1") (pinfunction "P$1_P$1") (pintype "bidirectional"))
    )
  )
)
